# ASIC_3.net
KiCad netlist of a schematic drawn in Altium Designer
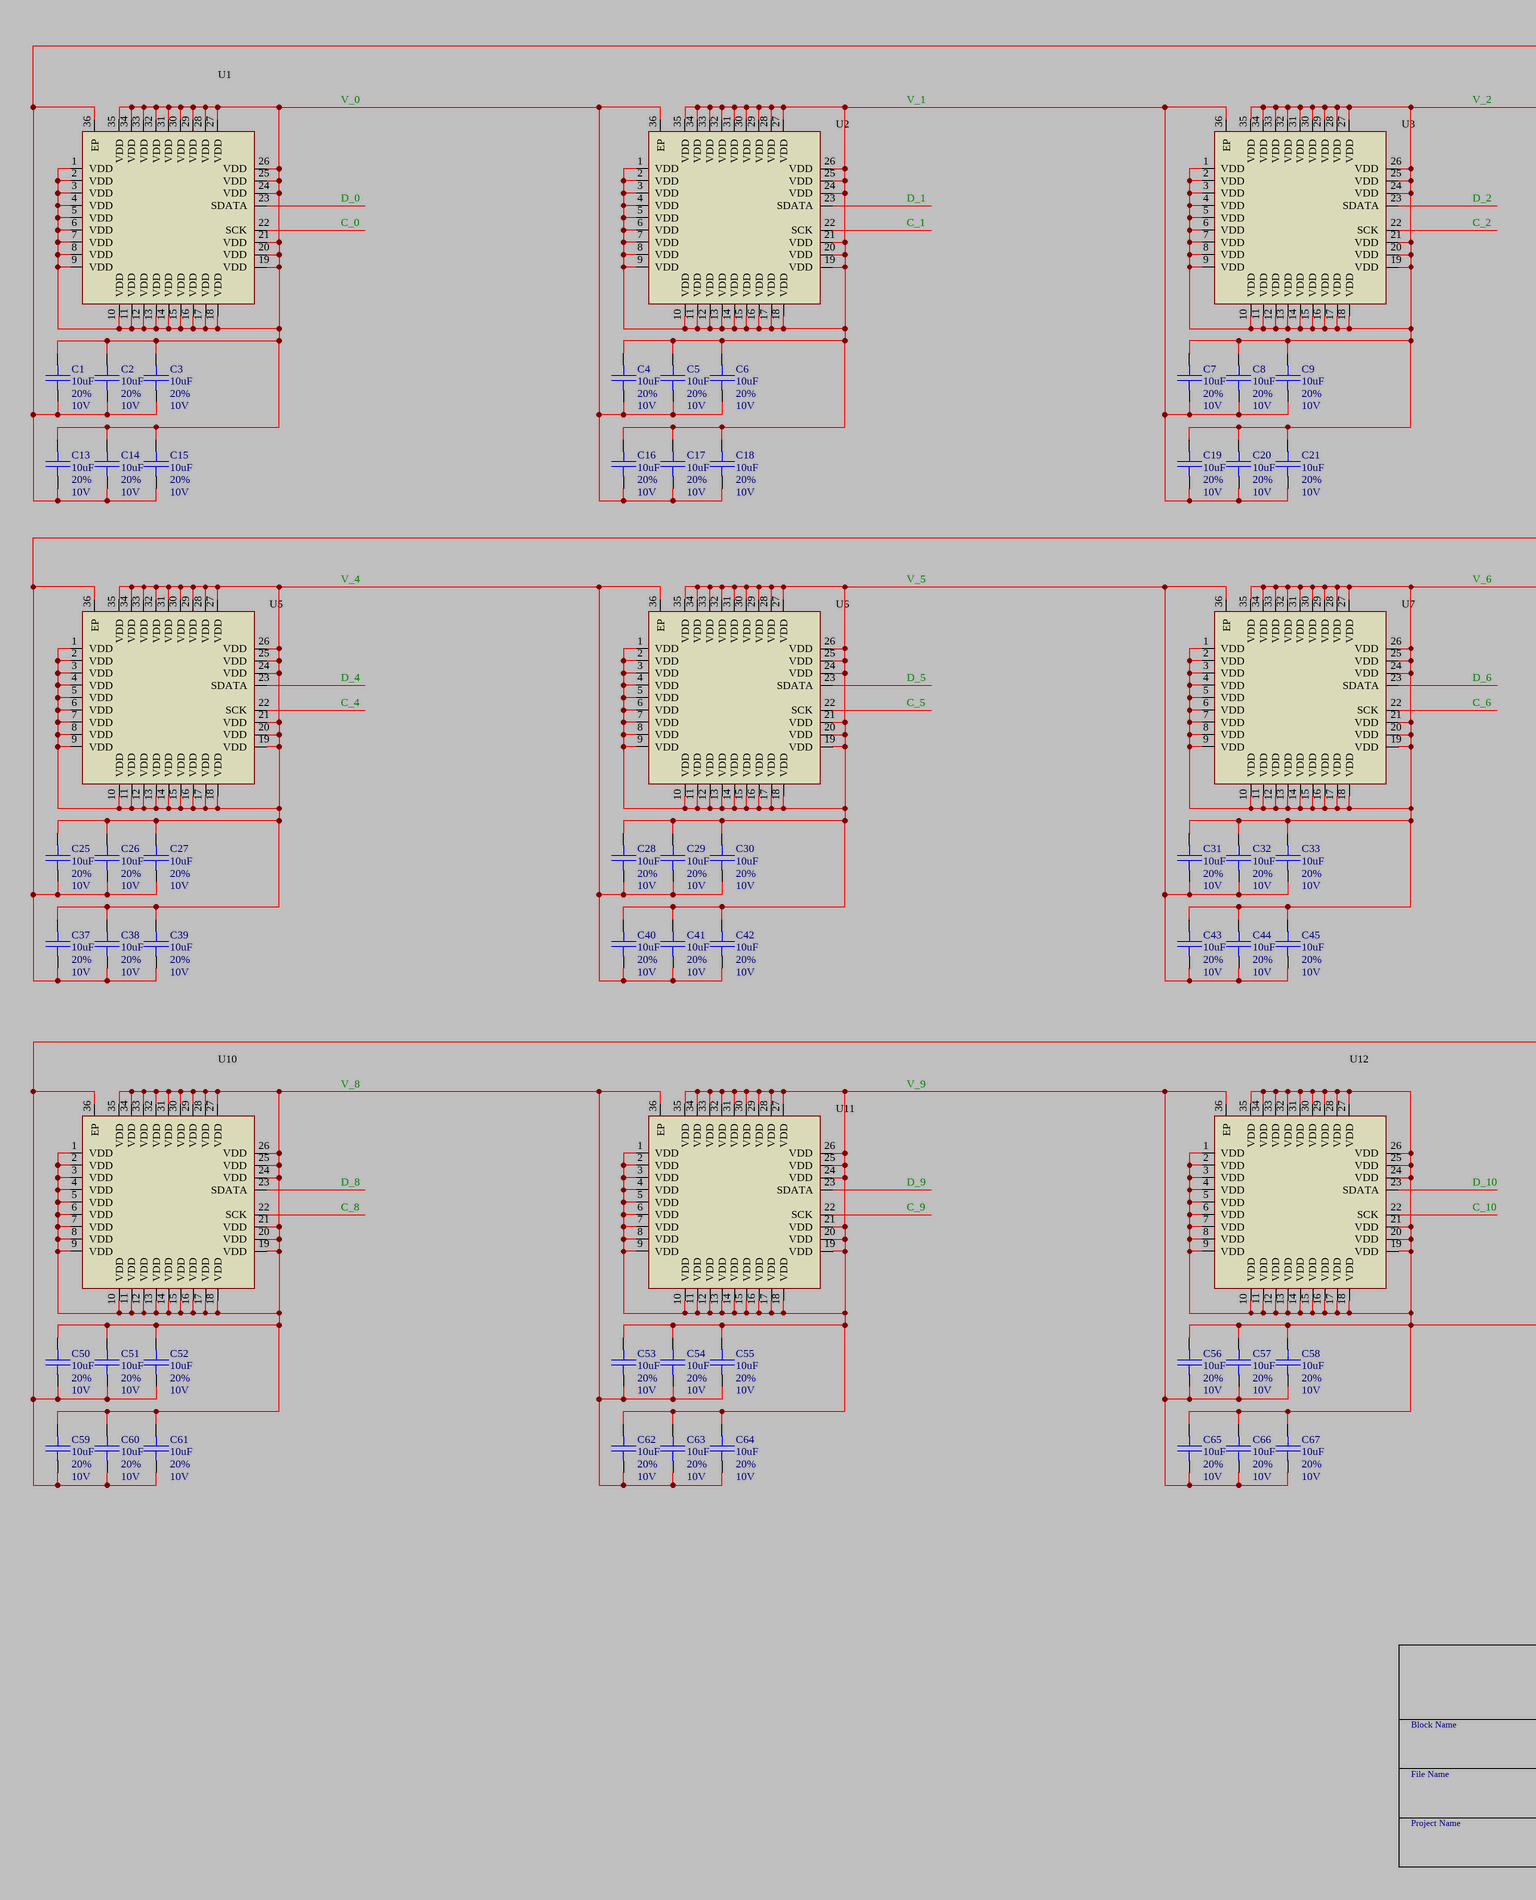
[diagram p0: ASIC_3.SchDoc, left]
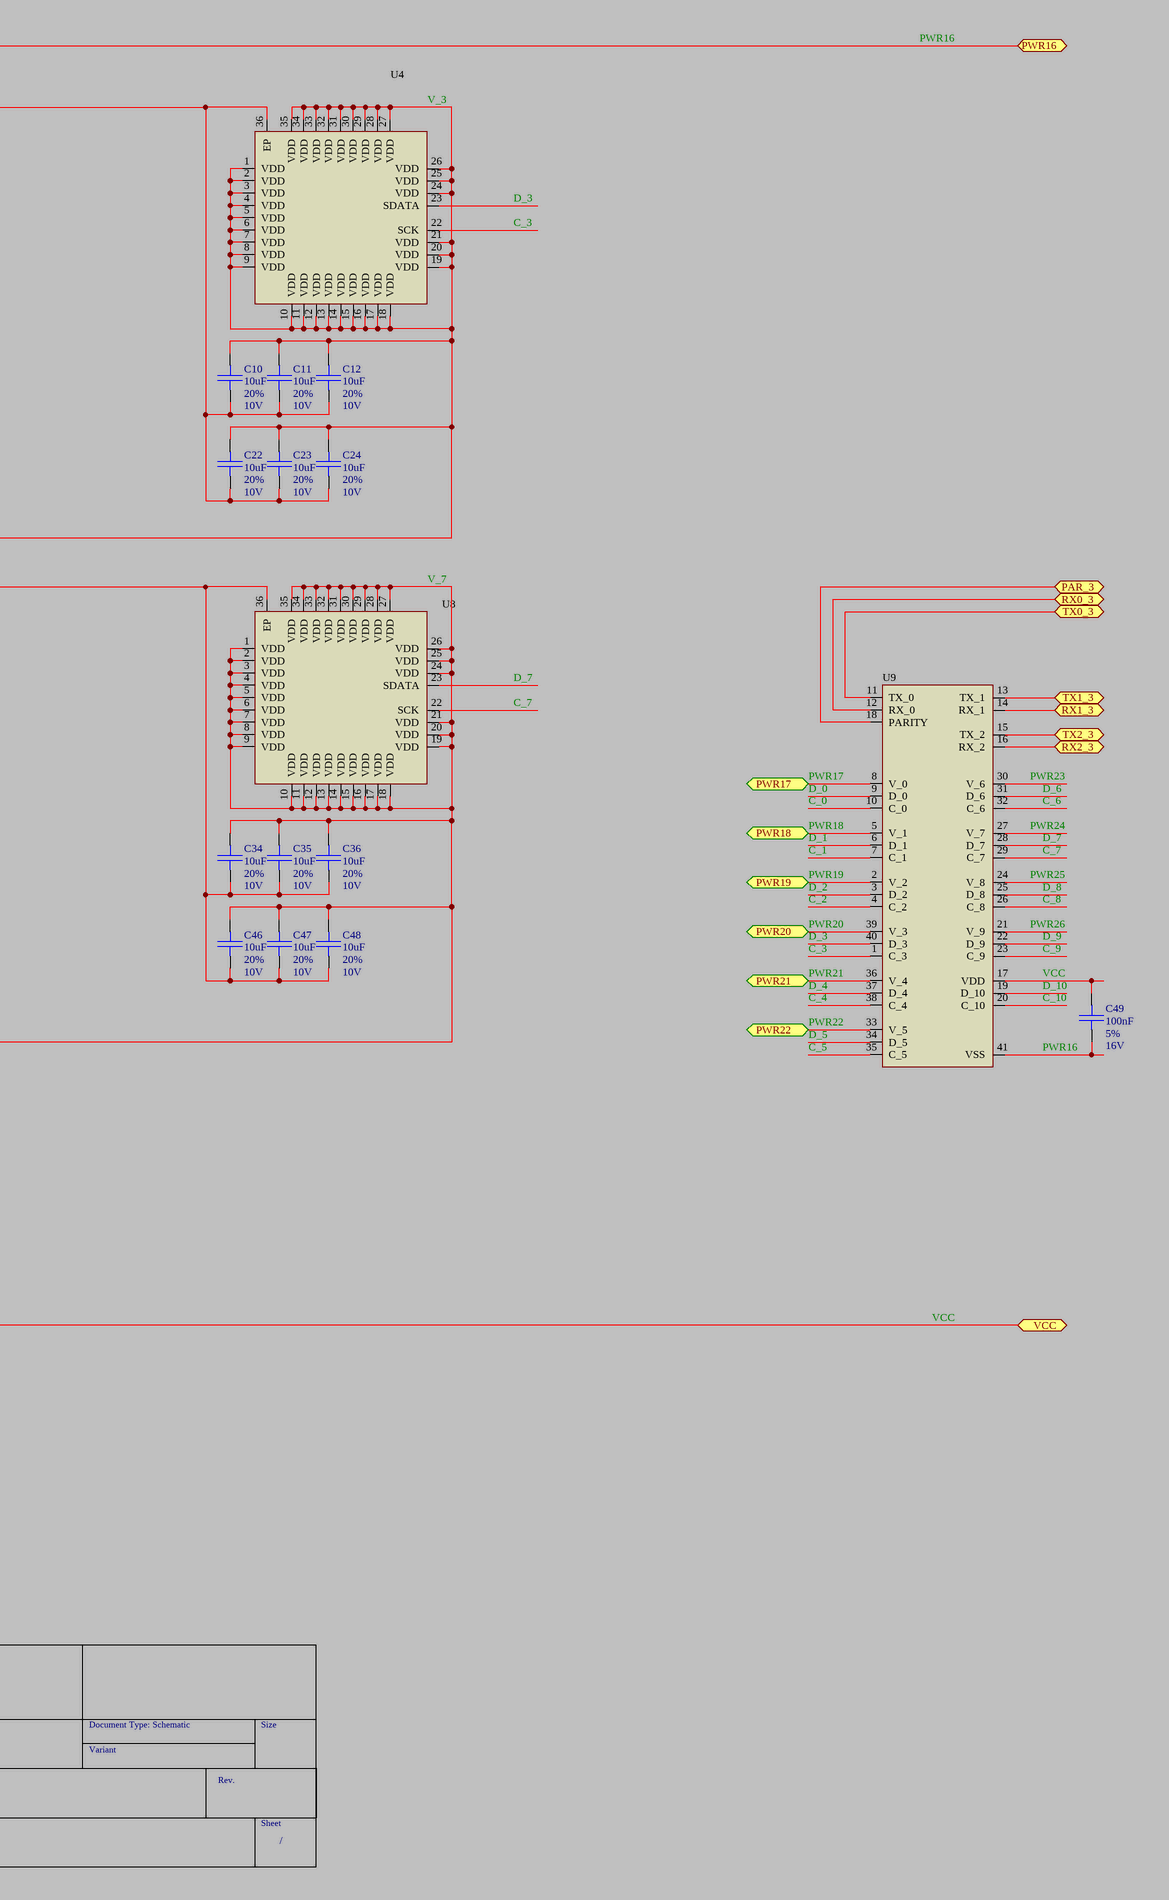
[diagram p1: ASIC_3.SchDoc, right]

(export (version "E")
  (design (tool "Eeschema 10.0.6"))
  (components
    (comp (ref "C1")
      (value "C")
      (footprint "SMD_0402_CAPC1005X70N")
      (fields
        (field (name "DB_PART_NUMBER") "CAP000047481")
        (field (name "DB_VALUE") "10uF")
        (field (name "DB_TOLERANCE") "20%")
        (field (name "DB_VOLTAGE") "10V")
        (field (name "DB_MANUFACTURER_PART") "SAMSUNG    CL05A106MP5NUNC")
        (field (name "DB_APPROVED_BY") "VSN")
      )
      (libsource (lib "Database_Libs1") (part "C"))
    )
    (comp (ref "C2")
      (value "C")
      (footprint "SMD_0402_CAPC1005X70N")
      (fields
        (field (name "DB_PART_NUMBER") "CAP000047481")
        (field (name "DB_VALUE") "10uF")
        (field (name "DB_TOLERANCE") "20%")
        (field (name "DB_VOLTAGE") "10V")
        (field (name "DB_MANUFACTURER_PART") "SAMSUNG    CL05A106MP5NUNC")
        (field (name "DB_APPROVED_BY") "VSN")
      )
      (libsource (lib "Database_Libs1") (part "C"))
    )
    (comp (ref "C3")
      (value "C")
      (footprint "SMD_0402_CAPC1005X70N")
      (fields
        (field (name "DB_PART_NUMBER") "CAP000047481")
        (field (name "DB_VALUE") "10uF")
        (field (name "DB_TOLERANCE") "20%")
        (field (name "DB_VOLTAGE") "10V")
        (field (name "DB_MANUFACTURER_PART") "SAMSUNG    CL05A106MP5NUNC")
        (field (name "DB_APPROVED_BY") "VSN")
      )
      (libsource (lib "Database_Libs1") (part "C"))
    )
    (comp (ref "C4")
      (value "C")
      (footprint "SMD_0402_CAPC1005X70N")
      (fields
        (field (name "DB_PART_NUMBER") "CAP000047481")
        (field (name "DB_VALUE") "10uF")
        (field (name "DB_TOLERANCE") "20%")
        (field (name "DB_VOLTAGE") "10V")
        (field (name "DB_MANUFACTURER_PART") "SAMSUNG    CL05A106MP5NUNC")
        (field (name "DB_APPROVED_BY") "VSN")
      )
      (libsource (lib "Database_Libs1") (part "C"))
    )
    (comp (ref "C5")
      (value "C")
      (footprint "SMD_0402_CAPC1005X70N")
      (fields
        (field (name "DB_PART_NUMBER") "CAP000047481")
        (field (name "DB_VALUE") "10uF")
        (field (name "DB_TOLERANCE") "20%")
        (field (name "DB_VOLTAGE") "10V")
        (field (name "DB_MANUFACTURER_PART") "SAMSUNG    CL05A106MP5NUNC")
        (field (name "DB_APPROVED_BY") "VSN")
      )
      (libsource (lib "Database_Libs1") (part "C"))
    )
    (comp (ref "C6")
      (value "C")
      (footprint "SMD_0402_CAPC1005X70N")
      (fields
        (field (name "DB_PART_NUMBER") "CAP000047481")
        (field (name "DB_VALUE") "10uF")
        (field (name "DB_TOLERANCE") "20%")
        (field (name "DB_VOLTAGE") "10V")
        (field (name "DB_MANUFACTURER_PART") "SAMSUNG    CL05A106MP5NUNC")
        (field (name "DB_APPROVED_BY") "VSN")
      )
      (libsource (lib "Database_Libs1") (part "C"))
    )
    (comp (ref "C7")
      (value "C")
      (footprint "SMD_0402_CAPC1005X70N")
      (fields
        (field (name "DB_PART_NUMBER") "CAP000047481")
        (field (name "DB_VALUE") "10uF")
        (field (name "DB_TOLERANCE") "20%")
        (field (name "DB_VOLTAGE") "10V")
        (field (name "DB_MANUFACTURER_PART") "SAMSUNG    CL05A106MP5NUNC")
        (field (name "DB_APPROVED_BY") "VSN")
      )
      (libsource (lib "Database_Libs1") (part "C"))
    )
    (comp (ref "C8")
      (value "C")
      (footprint "SMD_0402_CAPC1005X70N")
      (fields
        (field (name "DB_PART_NUMBER") "CAP000047481")
        (field (name "DB_VALUE") "10uF")
        (field (name "DB_TOLERANCE") "20%")
        (field (name "DB_VOLTAGE") "10V")
        (field (name "DB_MANUFACTURER_PART") "SAMSUNG    CL05A106MP5NUNC")
        (field (name "DB_APPROVED_BY") "VSN")
      )
      (libsource (lib "Database_Libs1") (part "C"))
    )
    (comp (ref "C9")
      (value "C")
      (footprint "SMD_0402_CAPC1005X70N")
      (fields
        (field (name "DB_PART_NUMBER") "CAP000047481")
        (field (name "DB_VALUE") "10uF")
        (field (name "DB_TOLERANCE") "20%")
        (field (name "DB_VOLTAGE") "10V")
        (field (name "DB_MANUFACTURER_PART") "SAMSUNG    CL05A106MP5NUNC")
        (field (name "DB_APPROVED_BY") "VSN")
      )
      (libsource (lib "Database_Libs1") (part "C"))
    )
    (comp (ref "C10")
      (value "C")
      (footprint "SMD_0402_CAPC1005X70N")
      (fields
        (field (name "DB_PART_NUMBER") "CAP000047481")
        (field (name "DB_VALUE") "10uF")
        (field (name "DB_TOLERANCE") "20%")
        (field (name "DB_VOLTAGE") "10V")
        (field (name "DB_MANUFACTURER_PART") "SAMSUNG    CL05A106MP5NUNC")
        (field (name "DB_APPROVED_BY") "VSN")
      )
      (libsource (lib "Database_Libs1") (part "C"))
    )
    (comp (ref "C11")
      (value "C")
      (footprint "SMD_0402_CAPC1005X70N")
      (fields
        (field (name "DB_PART_NUMBER") "CAP000047481")
        (field (name "DB_VALUE") "10uF")
        (field (name "DB_TOLERANCE") "20%")
        (field (name "DB_VOLTAGE") "10V")
        (field (name "DB_MANUFACTURER_PART") "SAMSUNG    CL05A106MP5NUNC")
        (field (name "DB_APPROVED_BY") "VSN")
      )
      (libsource (lib "Database_Libs1") (part "C"))
    )
    (comp (ref "C12")
      (value "C")
      (footprint "SMD_0402_CAPC1005X70N")
      (fields
        (field (name "DB_PART_NUMBER") "CAP000047481")
        (field (name "DB_VALUE") "10uF")
        (field (name "DB_TOLERANCE") "20%")
        (field (name "DB_VOLTAGE") "10V")
        (field (name "DB_MANUFACTURER_PART") "SAMSUNG    CL05A106MP5NUNC")
        (field (name "DB_APPROVED_BY") "VSN")
      )
      (libsource (lib "Database_Libs1") (part "C"))
    )
    (comp (ref "C13")
      (value "C")
      (footprint "SMD_0402_CAPC1005X70N")
      (fields
        (field (name "DB_PART_NUMBER") "CAP000047481")
        (field (name "DB_VALUE") "10uF")
        (field (name "DB_TOLERANCE") "20%")
        (field (name "DB_VOLTAGE") "10V")
        (field (name "DB_MANUFACTURER_PART") "SAMSUNG    CL05A106MP5NUNC")
        (field (name "DB_APPROVED_BY") "VSN")
      )
      (libsource (lib "Database_Libs1") (part "C"))
    )
    (comp (ref "C14")
      (value "C")
      (footprint "SMD_0402_CAPC1005X70N")
      (fields
        (field (name "DB_PART_NUMBER") "CAP000047481")
        (field (name "DB_VALUE") "10uF")
        (field (name "DB_TOLERANCE") "20%")
        (field (name "DB_VOLTAGE") "10V")
        (field (name "DB_MANUFACTURER_PART") "SAMSUNG    CL05A106MP5NUNC")
        (field (name "DB_APPROVED_BY") "VSN")
      )
      (libsource (lib "Database_Libs1") (part "C"))
    )
    (comp (ref "C15")
      (value "C")
      (footprint "SMD_0402_CAPC1005X70N")
      (fields
        (field (name "DB_PART_NUMBER") "CAP000047481")
        (field (name "DB_VALUE") "10uF")
        (field (name "DB_TOLERANCE") "20%")
        (field (name "DB_VOLTAGE") "10V")
        (field (name "DB_MANUFACTURER_PART") "SAMSUNG    CL05A106MP5NUNC")
        (field (name "DB_APPROVED_BY") "VSN")
      )
      (libsource (lib "Database_Libs1") (part "C"))
    )
    (comp (ref "C16")
      (value "C")
      (footprint "SMD_0402_CAPC1005X70N")
      (fields
        (field (name "DB_PART_NUMBER") "CAP000047481")
        (field (name "DB_VALUE") "10uF")
        (field (name "DB_TOLERANCE") "20%")
        (field (name "DB_VOLTAGE") "10V")
        (field (name "DB_MANUFACTURER_PART") "SAMSUNG    CL05A106MP5NUNC")
        (field (name "DB_APPROVED_BY") "VSN")
      )
      (libsource (lib "Database_Libs1") (part "C"))
    )
    (comp (ref "C17")
      (value "C")
      (footprint "SMD_0402_CAPC1005X70N")
      (fields
        (field (name "DB_PART_NUMBER") "CAP000047481")
        (field (name "DB_VALUE") "10uF")
        (field (name "DB_TOLERANCE") "20%")
        (field (name "DB_VOLTAGE") "10V")
        (field (name "DB_MANUFACTURER_PART") "SAMSUNG    CL05A106MP5NUNC")
        (field (name "DB_APPROVED_BY") "VSN")
      )
      (libsource (lib "Database_Libs1") (part "C"))
    )
    (comp (ref "C18")
      (value "C")
      (footprint "SMD_0402_CAPC1005X70N")
      (fields
        (field (name "DB_PART_NUMBER") "CAP000047481")
        (field (name "DB_VALUE") "10uF")
        (field (name "DB_TOLERANCE") "20%")
        (field (name "DB_VOLTAGE") "10V")
        (field (name "DB_MANUFACTURER_PART") "SAMSUNG    CL05A106MP5NUNC")
        (field (name "DB_APPROVED_BY") "VSN")
      )
      (libsource (lib "Database_Libs1") (part "C"))
    )
    (comp (ref "C19")
      (value "C")
      (footprint "SMD_0402_CAPC1005X70N")
      (fields
        (field (name "DB_PART_NUMBER") "CAP000047481")
        (field (name "DB_VALUE") "10uF")
        (field (name "DB_TOLERANCE") "20%")
        (field (name "DB_VOLTAGE") "10V")
        (field (name "DB_MANUFACTURER_PART") "SAMSUNG    CL05A106MP5NUNC")
        (field (name "DB_APPROVED_BY") "VSN")
      )
      (libsource (lib "Database_Libs1") (part "C"))
    )
    (comp (ref "C20")
      (value "C")
      (footprint "SMD_0402_CAPC1005X70N")
      (fields
        (field (name "DB_PART_NUMBER") "CAP000047481")
        (field (name "DB_VALUE") "10uF")
        (field (name "DB_TOLERANCE") "20%")
        (field (name "DB_VOLTAGE") "10V")
        (field (name "DB_MANUFACTURER_PART") "SAMSUNG    CL05A106MP5NUNC")
        (field (name "DB_APPROVED_BY") "VSN")
      )
      (libsource (lib "Database_Libs1") (part "C"))
    )
    (comp (ref "C21")
      (value "C")
      (footprint "SMD_0402_CAPC1005X70N")
      (fields
        (field (name "DB_PART_NUMBER") "CAP000047481")
        (field (name "DB_VALUE") "10uF")
        (field (name "DB_TOLERANCE") "20%")
        (field (name "DB_VOLTAGE") "10V")
        (field (name "DB_MANUFACTURER_PART") "SAMSUNG    CL05A106MP5NUNC")
        (field (name "DB_APPROVED_BY") "VSN")
      )
      (libsource (lib "Database_Libs1") (part "C"))
    )
    (comp (ref "C22")
      (value "C")
      (footprint "SMD_0402_CAPC1005X70N")
      (fields
        (field (name "DB_PART_NUMBER") "CAP000047481")
        (field (name "DB_VALUE") "10uF")
        (field (name "DB_TOLERANCE") "20%")
        (field (name "DB_VOLTAGE") "10V")
        (field (name "DB_MANUFACTURER_PART") "SAMSUNG    CL05A106MP5NUNC")
        (field (name "DB_APPROVED_BY") "VSN")
      )
      (libsource (lib "Database_Libs1") (part "C"))
    )
    (comp (ref "C23")
      (value "C")
      (footprint "SMD_0402_CAPC1005X70N")
      (fields
        (field (name "DB_PART_NUMBER") "CAP000047481")
        (field (name "DB_VALUE") "10uF")
        (field (name "DB_TOLERANCE") "20%")
        (field (name "DB_VOLTAGE") "10V")
        (field (name "DB_MANUFACTURER_PART") "SAMSUNG    CL05A106MP5NUNC")
        (field (name "DB_APPROVED_BY") "VSN")
      )
      (libsource (lib "Database_Libs1") (part "C"))
    )
    (comp (ref "C24")
      (value "C")
      (footprint "SMD_0402_CAPC1005X70N")
      (fields
        (field (name "DB_PART_NUMBER") "CAP000047481")
        (field (name "DB_VALUE") "10uF")
        (field (name "DB_TOLERANCE") "20%")
        (field (name "DB_VOLTAGE") "10V")
        (field (name "DB_MANUFACTURER_PART") "SAMSUNG    CL05A106MP5NUNC")
        (field (name "DB_APPROVED_BY") "VSN")
      )
      (libsource (lib "Database_Libs1") (part "C"))
    )
    (comp (ref "C25")
      (value "C")
      (footprint "SMD_0402_CAPC1005X70N")
      (fields
        (field (name "DB_PART_NUMBER") "CAP000047481")
        (field (name "DB_VALUE") "10uF")
        (field (name "DB_TOLERANCE") "20%")
        (field (name "DB_VOLTAGE") "10V")
        (field (name "DB_MANUFACTURER_PART") "SAMSUNG    CL05A106MP5NUNC")
        (field (name "DB_APPROVED_BY") "VSN")
      )
      (libsource (lib "Database_Libs1") (part "C"))
    )
    (comp (ref "C26")
      (value "C")
      (footprint "SMD_0402_CAPC1005X70N")
      (fields
        (field (name "DB_PART_NUMBER") "CAP000047481")
        (field (name "DB_VALUE") "10uF")
        (field (name "DB_TOLERANCE") "20%")
        (field (name "DB_VOLTAGE") "10V")
        (field (name "DB_MANUFACTURER_PART") "SAMSUNG    CL05A106MP5NUNC")
        (field (name "DB_APPROVED_BY") "VSN")
      )
      (libsource (lib "Database_Libs1") (part "C"))
    )
    (comp (ref "C27")
      (value "C")
      (footprint "SMD_0402_CAPC1005X70N")
      (fields
        (field (name "DB_PART_NUMBER") "CAP000047481")
        (field (name "DB_VALUE") "10uF")
        (field (name "DB_TOLERANCE") "20%")
        (field (name "DB_VOLTAGE") "10V")
        (field (name "DB_MANUFACTURER_PART") "SAMSUNG    CL05A106MP5NUNC")
        (field (name "DB_APPROVED_BY") "VSN")
      )
      (libsource (lib "Database_Libs1") (part "C"))
    )
    (comp (ref "C28")
      (value "C")
      (footprint "SMD_0402_CAPC1005X70N")
      (fields
        (field (name "DB_PART_NUMBER") "CAP000047481")
        (field (name "DB_VALUE") "10uF")
        (field (name "DB_TOLERANCE") "20%")
        (field (name "DB_VOLTAGE") "10V")
        (field (name "DB_MANUFACTURER_PART") "SAMSUNG    CL05A106MP5NUNC")
        (field (name "DB_APPROVED_BY") "VSN")
      )
      (libsource (lib "Database_Libs1") (part "C"))
    )
    (comp (ref "C29")
      (value "C")
      (footprint "SMD_0402_CAPC1005X70N")
      (fields
        (field (name "DB_PART_NUMBER") "CAP000047481")
        (field (name "DB_VALUE") "10uF")
        (field (name "DB_TOLERANCE") "20%")
        (field (name "DB_VOLTAGE") "10V")
        (field (name "DB_MANUFACTURER_PART") "SAMSUNG    CL05A106MP5NUNC")
        (field (name "DB_APPROVED_BY") "VSN")
      )
      (libsource (lib "Database_Libs1") (part "C"))
    )
    (comp (ref "C30")
      (value "C")
      (footprint "SMD_0402_CAPC1005X70N")
      (fields
        (field (name "DB_PART_NUMBER") "CAP000047481")
        (field (name "DB_VALUE") "10uF")
        (field (name "DB_TOLERANCE") "20%")
        (field (name "DB_VOLTAGE") "10V")
        (field (name "DB_MANUFACTURER_PART") "SAMSUNG    CL05A106MP5NUNC")
        (field (name "DB_APPROVED_BY") "VSN")
      )
      (libsource (lib "Database_Libs1") (part "C"))
    )
    (comp (ref "C31")
      (value "C")
      (footprint "SMD_0402_CAPC1005X70N")
      (fields
        (field (name "DB_PART_NUMBER") "CAP000047481")
        (field (name "DB_VALUE") "10uF")
        (field (name "DB_TOLERANCE") "20%")
        (field (name "DB_VOLTAGE") "10V")
        (field (name "DB_MANUFACTURER_PART") "SAMSUNG    CL05A106MP5NUNC")
        (field (name "DB_APPROVED_BY") "VSN")
      )
      (libsource (lib "Database_Libs1") (part "C"))
    )
    (comp (ref "C32")
      (value "C")
      (footprint "SMD_0402_CAPC1005X70N")
      (fields
        (field (name "DB_PART_NUMBER") "CAP000047481")
        (field (name "DB_VALUE") "10uF")
        (field (name "DB_TOLERANCE") "20%")
        (field (name "DB_VOLTAGE") "10V")
        (field (name "DB_MANUFACTURER_PART") "SAMSUNG    CL05A106MP5NUNC")
        (field (name "DB_APPROVED_BY") "VSN")
      )
      (libsource (lib "Database_Libs1") (part "C"))
    )
    (comp (ref "C33")
      (value "C")
      (footprint "SMD_0402_CAPC1005X70N")
      (fields
        (field (name "DB_PART_NUMBER") "CAP000047481")
        (field (name "DB_VALUE") "10uF")
        (field (name "DB_TOLERANCE") "20%")
        (field (name "DB_VOLTAGE") "10V")
        (field (name "DB_MANUFACTURER_PART") "SAMSUNG    CL05A106MP5NUNC")
        (field (name "DB_APPROVED_BY") "VSN")
      )
      (libsource (lib "Database_Libs1") (part "C"))
    )
    (comp (ref "C34")
      (value "C")
      (footprint "SMD_0402_CAPC1005X70N")
      (fields
        (field (name "DB_PART_NUMBER") "CAP000047481")
        (field (name "DB_VALUE") "10uF")
        (field (name "DB_TOLERANCE") "20%")
        (field (name "DB_VOLTAGE") "10V")
        (field (name "DB_MANUFACTURER_PART") "SAMSUNG    CL05A106MP5NUNC")
        (field (name "DB_APPROVED_BY") "VSN")
      )
      (libsource (lib "Database_Libs1") (part "C"))
    )
    (comp (ref "C35")
      (value "C")
      (footprint "SMD_0402_CAPC1005X70N")
      (fields
        (field (name "DB_PART_NUMBER") "CAP000047481")
        (field (name "DB_VALUE") "10uF")
        (field (name "DB_TOLERANCE") "20%")
        (field (name "DB_VOLTAGE") "10V")
        (field (name "DB_MANUFACTURER_PART") "SAMSUNG    CL05A106MP5NUNC")
        (field (name "DB_APPROVED_BY") "VSN")
      )
      (libsource (lib "Database_Libs1") (part "C"))
    )
    (comp (ref "C36")
      (value "C")
      (footprint "SMD_0402_CAPC1005X70N")
      (fields
        (field (name "DB_PART_NUMBER") "CAP000047481")
        (field (name "DB_VALUE") "10uF")
        (field (name "DB_TOLERANCE") "20%")
        (field (name "DB_VOLTAGE") "10V")
        (field (name "DB_MANUFACTURER_PART") "SAMSUNG    CL05A106MP5NUNC")
        (field (name "DB_APPROVED_BY") "VSN")
      )
      (libsource (lib "Database_Libs1") (part "C"))
    )
    (comp (ref "C37")
      (value "C")
      (footprint "SMD_0402_CAPC1005X70N")
      (fields
        (field (name "DB_PART_NUMBER") "CAP000047481")
        (field (name "DB_VALUE") "10uF")
        (field (name "DB_TOLERANCE") "20%")
        (field (name "DB_VOLTAGE") "10V")
        (field (name "DB_MANUFACTURER_PART") "SAMSUNG    CL05A106MP5NUNC")
        (field (name "DB_APPROVED_BY") "VSN")
      )
      (libsource (lib "Database_Libs1") (part "C"))
    )
    (comp (ref "C38")
      (value "C")
      (footprint "SMD_0402_CAPC1005X70N")
      (fields
        (field (name "DB_PART_NUMBER") "CAP000047481")
        (field (name "DB_VALUE") "10uF")
        (field (name "DB_TOLERANCE") "20%")
        (field (name "DB_VOLTAGE") "10V")
        (field (name "DB_MANUFACTURER_PART") "SAMSUNG    CL05A106MP5NUNC")
        (field (name "DB_APPROVED_BY") "VSN")
      )
      (libsource (lib "Database_Libs1") (part "C"))
    )
    (comp (ref "C39")
      (value "C")
      (footprint "SMD_0402_CAPC1005X70N")
      (fields
        (field (name "DB_PART_NUMBER") "CAP000047481")
        (field (name "DB_VALUE") "10uF")
        (field (name "DB_TOLERANCE") "20%")
        (field (name "DB_VOLTAGE") "10V")
        (field (name "DB_MANUFACTURER_PART") "SAMSUNG    CL05A106MP5NUNC")
        (field (name "DB_APPROVED_BY") "VSN")
      )
      (libsource (lib "Database_Libs1") (part "C"))
    )
    (comp (ref "C40")
      (value "C")
      (footprint "SMD_0402_CAPC1005X70N")
      (fields
        (field (name "DB_PART_NUMBER") "CAP000047481")
        (field (name "DB_VALUE") "10uF")
        (field (name "DB_TOLERANCE") "20%")
        (field (name "DB_VOLTAGE") "10V")
        (field (name "DB_MANUFACTURER_PART") "SAMSUNG    CL05A106MP5NUNC")
        (field (name "DB_APPROVED_BY") "VSN")
      )
      (libsource (lib "Database_Libs1") (part "C"))
    )
    (comp (ref "C41")
      (value "C")
      (footprint "SMD_0402_CAPC1005X70N")
      (fields
        (field (name "DB_PART_NUMBER") "CAP000047481")
        (field (name "DB_VALUE") "10uF")
        (field (name "DB_TOLERANCE") "20%")
        (field (name "DB_VOLTAGE") "10V")
        (field (name "DB_MANUFACTURER_PART") "SAMSUNG    CL05A106MP5NUNC")
        (field (name "DB_APPROVED_BY") "VSN")
      )
      (libsource (lib "Database_Libs1") (part "C"))
    )
    (comp (ref "C42")
      (value "C")
      (footprint "SMD_0402_CAPC1005X70N")
      (fields
        (field (name "DB_PART_NUMBER") "CAP000047481")
        (field (name "DB_VALUE") "10uF")
        (field (name "DB_TOLERANCE") "20%")
        (field (name "DB_VOLTAGE") "10V")
        (field (name "DB_MANUFACTURER_PART") "SAMSUNG    CL05A106MP5NUNC")
        (field (name "DB_APPROVED_BY") "VSN")
      )
      (libsource (lib "Database_Libs1") (part "C"))
    )
    (comp (ref "C43")
      (value "C")
      (footprint "SMD_0402_CAPC1005X70N")
      (fields
        (field (name "DB_PART_NUMBER") "CAP000047481")
        (field (name "DB_VALUE") "10uF")
        (field (name "DB_TOLERANCE") "20%")
        (field (name "DB_VOLTAGE") "10V")
        (field (name "DB_MANUFACTURER_PART") "SAMSUNG    CL05A106MP5NUNC")
        (field (name "DB_APPROVED_BY") "VSN")
      )
      (libsource (lib "Database_Libs1") (part "C"))
    )
    (comp (ref "C44")
      (value "C")
      (footprint "SMD_0402_CAPC1005X70N")
      (fields
        (field (name "DB_PART_NUMBER") "CAP000047481")
        (field (name "DB_VALUE") "10uF")
        (field (name "DB_TOLERANCE") "20%")
        (field (name "DB_VOLTAGE") "10V")
        (field (name "DB_MANUFACTURER_PART") "SAMSUNG    CL05A106MP5NUNC")
        (field (name "DB_APPROVED_BY") "VSN")
      )
      (libsource (lib "Database_Libs1") (part "C"))
    )
    (comp (ref "C45")
      (value "C")
      (footprint "SMD_0402_CAPC1005X70N")
      (fields
        (field (name "DB_PART_NUMBER") "CAP000047481")
        (field (name "DB_VALUE") "10uF")
        (field (name "DB_TOLERANCE") "20%")
        (field (name "DB_VOLTAGE") "10V")
        (field (name "DB_MANUFACTURER_PART") "SAMSUNG    CL05A106MP5NUNC")
        (field (name "DB_APPROVED_BY") "VSN")
      )
      (libsource (lib "Database_Libs1") (part "C"))
    )
    (comp (ref "C46")
      (value "C")
      (footprint "SMD_0402_CAPC1005X70N")
      (fields
        (field (name "DB_PART_NUMBER") "CAP000047481")
        (field (name "DB_VALUE") "10uF")
        (field (name "DB_TOLERANCE") "20%")
        (field (name "DB_VOLTAGE") "10V")
        (field (name "DB_MANUFACTURER_PART") "SAMSUNG    CL05A106MP5NUNC")
        (field (name "DB_APPROVED_BY") "VSN")
      )
      (libsource (lib "Database_Libs1") (part "C"))
    )
    (comp (ref "C47")
      (value "C")
      (footprint "SMD_0402_CAPC1005X70N")
      (fields
        (field (name "DB_PART_NUMBER") "CAP000047481")
        (field (name "DB_VALUE") "10uF")
        (field (name "DB_TOLERANCE") "20%")
        (field (name "DB_VOLTAGE") "10V")
        (field (name "DB_MANUFACTURER_PART") "SAMSUNG    CL05A106MP5NUNC")
        (field (name "DB_APPROVED_BY") "VSN")
      )
      (libsource (lib "Database_Libs1") (part "C"))
    )
    (comp (ref "C48")
      (value "C")
      (footprint "SMD_0402_CAPC1005X70N")
      (fields
        (field (name "DB_PART_NUMBER") "CAP000047481")
        (field (name "DB_VALUE") "10uF")
        (field (name "DB_TOLERANCE") "20%")
        (field (name "DB_VOLTAGE") "10V")
        (field (name "DB_MANUFACTURER_PART") "SAMSUNG    CL05A106MP5NUNC")
        (field (name "DB_APPROVED_BY") "VSN")
      )
      (libsource (lib "Database_Libs1") (part "C"))
    )
    (comp (ref "C49")
      (value "C")
      (footprint "SMD_0603_CAPC1608X95N")
      (fields
        (field (name "DB_PART_NUMBER") "CAP000027134")
        (field (name "DB_VALUE") "100nF")
        (field (name "DB_TOLERANCE") "5%")
        (field (name "DB_VOLTAGE") "16V")
        (field (name "DB_MANUFACTURER_PART") "KEMET    C0603C104J4RAC")
      )
      (libsource (lib "Database_Libs1") (part "C"))
    )
    (comp (ref "C50")
      (value "C")
      (footprint "SMD_0402_CAPC1005X70N")
      (fields
        (field (name "DB_PART_NUMBER") "CAP000047481")
        (field (name "DB_VALUE") "10uF")
        (field (name "DB_TOLERANCE") "20%")
        (field (name "DB_VOLTAGE") "10V")
        (field (name "DB_MANUFACTURER_PART") "SAMSUNG    CL05A106MP5NUNC")
        (field (name "DB_APPROVED_BY") "VSN")
      )
      (libsource (lib "Database_Libs1") (part "C"))
    )
    (comp (ref "C51")
      (value "C")
      (footprint "SMD_0402_CAPC1005X70N")
      (fields
        (field (name "DB_PART_NUMBER") "CAP000047481")
        (field (name "DB_VALUE") "10uF")
        (field (name "DB_TOLERANCE") "20%")
        (field (name "DB_VOLTAGE") "10V")
        (field (name "DB_MANUFACTURER_PART") "SAMSUNG    CL05A106MP5NUNC")
        (field (name "DB_APPROVED_BY") "VSN")
      )
      (libsource (lib "Database_Libs1") (part "C"))
    )
    (comp (ref "C52")
      (value "C")
      (footprint "SMD_0402_CAPC1005X70N")
      (fields
        (field (name "DB_PART_NUMBER") "CAP000047481")
        (field (name "DB_VALUE") "10uF")
        (field (name "DB_TOLERANCE") "20%")
        (field (name "DB_VOLTAGE") "10V")
        (field (name "DB_MANUFACTURER_PART") "SAMSUNG    CL05A106MP5NUNC")
        (field (name "DB_APPROVED_BY") "VSN")
      )
      (libsource (lib "Database_Libs1") (part "C"))
    )
    (comp (ref "C53")
      (value "C")
      (footprint "SMD_0402_CAPC1005X70N")
      (fields
        (field (name "DB_PART_NUMBER") "CAP000047481")
        (field (name "DB_VALUE") "10uF")
        (field (name "DB_TOLERANCE") "20%")
        (field (name "DB_VOLTAGE") "10V")
        (field (name "DB_MANUFACTURER_PART") "SAMSUNG    CL05A106MP5NUNC")
        (field (name "DB_APPROVED_BY") "VSN")
      )
      (libsource (lib "Database_Libs1") (part "C"))
    )
    (comp (ref "C54")
      (value "C")
      (footprint "SMD_0402_CAPC1005X70N")
      (fields
        (field (name "DB_PART_NUMBER") "CAP000047481")
        (field (name "DB_VALUE") "10uF")
        (field (name "DB_TOLERANCE") "20%")
        (field (name "DB_VOLTAGE") "10V")
        (field (name "DB_MANUFACTURER_PART") "SAMSUNG    CL05A106MP5NUNC")
        (field (name "DB_APPROVED_BY") "VSN")
      )
      (libsource (lib "Database_Libs1") (part "C"))
    )
    (comp (ref "C55")
      (value "C")
      (footprint "SMD_0402_CAPC1005X70N")
      (fields
        (field (name "DB_PART_NUMBER") "CAP000047481")
        (field (name "DB_VALUE") "10uF")
        (field (name "DB_TOLERANCE") "20%")
        (field (name "DB_VOLTAGE") "10V")
        (field (name "DB_MANUFACTURER_PART") "SAMSUNG    CL05A106MP5NUNC")
        (field (name "DB_APPROVED_BY") "VSN")
      )
      (libsource (lib "Database_Libs1") (part "C"))
    )
    (comp (ref "C56")
      (value "C")
      (footprint "SMD_0402_CAPC1005X70N")
      (fields
        (field (name "DB_PART_NUMBER") "CAP000047481")
        (field (name "DB_VALUE") "10uF")
        (field (name "DB_TOLERANCE") "20%")
        (field (name "DB_VOLTAGE") "10V")
        (field (name "DB_MANUFACTURER_PART") "SAMSUNG    CL05A106MP5NUNC")
        (field (name "DB_APPROVED_BY") "VSN")
      )
      (libsource (lib "Database_Libs1") (part "C"))
    )
    (comp (ref "C57")
      (value "C")
      (footprint "SMD_0402_CAPC1005X70N")
      (fields
        (field (name "DB_PART_NUMBER") "CAP000047481")
        (field (name "DB_VALUE") "10uF")
        (field (name "DB_TOLERANCE") "20%")
        (field (name "DB_VOLTAGE") "10V")
        (field (name "DB_MANUFACTURER_PART") "SAMSUNG    CL05A106MP5NUNC")
        (field (name "DB_APPROVED_BY") "VSN")
      )
      (libsource (lib "Database_Libs1") (part "C"))
    )
    (comp (ref "C58")
      (value "C")
      (footprint "SMD_0402_CAPC1005X70N")
      (fields
        (field (name "DB_PART_NUMBER") "CAP000047481")
        (field (name "DB_VALUE") "10uF")
        (field (name "DB_TOLERANCE") "20%")
        (field (name "DB_VOLTAGE") "10V")
        (field (name "DB_MANUFACTURER_PART") "SAMSUNG    CL05A106MP5NUNC")
        (field (name "DB_APPROVED_BY") "VSN")
      )
      (libsource (lib "Database_Libs1") (part "C"))
    )
    (comp (ref "C59")
      (value "C")
      (footprint "SMD_0402_CAPC1005X70N")
      (fields
        (field (name "DB_PART_NUMBER") "CAP000047481")
        (field (name "DB_VALUE") "10uF")
        (field (name "DB_TOLERANCE") "20%")
        (field (name "DB_VOLTAGE") "10V")
        (field (name "DB_MANUFACTURER_PART") "SAMSUNG    CL05A106MP5NUNC")
        (field (name "DB_APPROVED_BY") "VSN")
      )
      (libsource (lib "Database_Libs1") (part "C"))
    )
    (comp (ref "C60")
      (value "C")
      (footprint "SMD_0402_CAPC1005X70N")
      (fields
        (field (name "DB_PART_NUMBER") "CAP000047481")
        (field (name "DB_VALUE") "10uF")
        (field (name "DB_TOLERANCE") "20%")
        (field (name "DB_VOLTAGE") "10V")
        (field (name "DB_MANUFACTURER_PART") "SAMSUNG    CL05A106MP5NUNC")
        (field (name "DB_APPROVED_BY") "VSN")
      )
      (libsource (lib "Database_Libs1") (part "C"))
    )
    (comp (ref "C61")
      (value "C")
      (footprint "SMD_0402_CAPC1005X70N")
      (fields
        (field (name "DB_PART_NUMBER") "CAP000047481")
        (field (name "DB_VALUE") "10uF")
        (field (name "DB_TOLERANCE") "20%")
        (field (name "DB_VOLTAGE") "10V")
        (field (name "DB_MANUFACTURER_PART") "SAMSUNG    CL05A106MP5NUNC")
        (field (name "DB_APPROVED_BY") "VSN")
      )
      (libsource (lib "Database_Libs1") (part "C"))
    )
    (comp (ref "C62")
      (value "C")
      (footprint "SMD_0402_CAPC1005X70N")
      (fields
        (field (name "DB_PART_NUMBER") "CAP000047481")
        (field (name "DB_VALUE") "10uF")
        (field (name "DB_TOLERANCE") "20%")
        (field (name "DB_VOLTAGE") "10V")
        (field (name "DB_MANUFACTURER_PART") "SAMSUNG    CL05A106MP5NUNC")
        (field (name "DB_APPROVED_BY") "VSN")
      )
      (libsource (lib "Database_Libs1") (part "C"))
    )
    (comp (ref "C63")
      (value "C")
      (footprint "SMD_0402_CAPC1005X70N")
      (fields
        (field (name "DB_PART_NUMBER") "CAP000047481")
        (field (name "DB_VALUE") "10uF")
        (field (name "DB_TOLERANCE") "20%")
        (field (name "DB_VOLTAGE") "10V")
        (field (name "DB_MANUFACTURER_PART") "SAMSUNG    CL05A106MP5NUNC")
        (field (name "DB_APPROVED_BY") "VSN")
      )
      (libsource (lib "Database_Libs1") (part "C"))
    )
    (comp (ref "C64")
      (value "C")
      (footprint "SMD_0402_CAPC1005X70N")
      (fields
        (field (name "DB_PART_NUMBER") "CAP000047481")
        (field (name "DB_VALUE") "10uF")
        (field (name "DB_TOLERANCE") "20%")
        (field (name "DB_VOLTAGE") "10V")
        (field (name "DB_MANUFACTURER_PART") "SAMSUNG    CL05A106MP5NUNC")
        (field (name "DB_APPROVED_BY") "VSN")
      )
      (libsource (lib "Database_Libs1") (part "C"))
    )
    (comp (ref "C65")
      (value "C")
      (footprint "SMD_0402_CAPC1005X70N")
      (fields
        (field (name "DB_PART_NUMBER") "CAP000047481")
        (field (name "DB_VALUE") "10uF")
        (field (name "DB_TOLERANCE") "20%")
        (field (name "DB_VOLTAGE") "10V")
        (field (name "DB_MANUFACTURER_PART") "SAMSUNG    CL05A106MP5NUNC")
        (field (name "DB_APPROVED_BY") "VSN")
      )
      (libsource (lib "Database_Libs1") (part "C"))
    )
    (comp (ref "C66")
      (value "C")
      (footprint "SMD_0402_CAPC1005X70N")
      (fields
        (field (name "DB_PART_NUMBER") "CAP000047481")
        (field (name "DB_VALUE") "10uF")
        (field (name "DB_TOLERANCE") "20%")
        (field (name "DB_VOLTAGE") "10V")
        (field (name "DB_MANUFACTURER_PART") "SAMSUNG    CL05A106MP5NUNC")
        (field (name "DB_APPROVED_BY") "VSN")
      )
      (libsource (lib "Database_Libs1") (part "C"))
    )
    (comp (ref "C67")
      (value "C")
      (footprint "SMD_0402_CAPC1005X70N")
      (fields
        (field (name "DB_PART_NUMBER") "CAP000047481")
        (field (name "DB_VALUE") "10uF")
        (field (name "DB_TOLERANCE") "20%")
        (field (name "DB_VOLTAGE") "10V")
        (field (name "DB_MANUFACTURER_PART") "SAMSUNG    CL05A106MP5NUNC")
        (field (name "DB_APPROVED_BY") "VSN")
      )
      (libsource (lib "Database_Libs1") (part "C"))
    )
    (comp (ref "U1")
      (value "IC_BITFURY16")
      (footprint "SMD_QFN50P600X600X175-36AN")
      (description "BitFury 2016 16 nm")
      (libsource (lib "BitCoin") (part "IC_BITFURY16"))
    )
    (comp (ref "U2")
      (value "IC_BITFURY16")
      (footprint "SMD_QFN50P600X600X175-36AN")
      (description "BitFury 2016 16 nm")
      (libsource (lib "BitCoin") (part "IC_BITFURY16"))
    )
    (comp (ref "U3")
      (value "IC_BITFURY16")
      (footprint "SMD_QFN50P600X600X175-36AN")
      (description "BitFury 2016 16 nm")
      (libsource (lib "BitCoin") (part "IC_BITFURY16"))
    )
    (comp (ref "U4")
      (value "IC_BITFURY16")
      (footprint "SMD_QFN50P600X600X175-36AN")
      (description "BitFury 2016 16 nm")
      (libsource (lib "BitCoin") (part "IC_BITFURY16"))
    )
    (comp (ref "U5")
      (value "IC_BITFURY16")
      (footprint "SMD_QFN50P600X600X175-36AN")
      (description "BitFury 2016 16 nm")
      (libsource (lib "BitCoin") (part "IC_BITFURY16"))
    )
    (comp (ref "U6")
      (value "IC_BITFURY16")
      (footprint "SMD_QFN50P600X600X175-36AN")
      (description "BitFury 2016 16 nm")
      (libsource (lib "BitCoin") (part "IC_BITFURY16"))
    )
    (comp (ref "U7")
      (value "IC_BITFURY16")
      (footprint "SMD_QFN50P600X600X175-36AN")
      (description "BitFury 2016 16 nm")
      (libsource (lib "BitCoin") (part "IC_BITFURY16"))
    )
    (comp (ref "U8")
      (value "IC_BITFURY16")
      (footprint "SMD_QFN50P600X600X175-36AN")
      (description "BitFury 2016 16 nm")
      (libsource (lib "BitCoin") (part "IC_BITFURY16"))
    )
    (comp (ref "U9")
      (value "IC_BTC250")
      (footprint "SMD_QFN40P500X500X80-41N")
      (fields (field (name "DB_MANUFACTURER_PART") "BTC250 QFN40 EP"))
      (libsource (lib "BitCoin") (part "IC_BTC250"))
    )
    (comp (ref "U10")
      (value "IC_BITFURY16")
      (footprint "SMD_QFN50P600X600X175-36AN")
      (description "BitFury 2016 16 nm")
      (libsource (lib "BitCoin") (part "IC_BITFURY16"))
    )
    (comp (ref "U11")
      (value "IC_BITFURY16")
      (footprint "SMD_QFN50P600X600X175-36AN")
      (description "BitFury 2016 16 nm")
      (libsource (lib "BitCoin") (part "IC_BITFURY16"))
    )
    (comp (ref "U12")
      (value "IC_BITFURY16")
      (footprint "SMD_QFN50P600X600X175-36AN")
      (description "BitFury 2016 16 nm")
      (libsource (lib "BitCoin") (part "IC_BITFURY16"))
    )
  )
  (nets
    (net (code "1") (name "/C_0") (class "Default")
      (node (ref "U1") (pin "22") (pinfunction "SCK_22") (pintype "passive"))
      (node (ref "U9") (pin "10") (pinfunction "C_0_10") (pintype "passive"))
    )
    (net (code "2") (name "/C_1") (class "Default")
      (node (ref "U2") (pin "22") (pinfunction "SCK_22") (pintype "passive"))
      (node (ref "U9") (pin "7") (pinfunction "C_1_7") (pintype "passive"))
    )
    (net (code "3") (name "/C_2") (class "Default")
      (node (ref "U3") (pin "22") (pinfunction "SCK_22") (pintype "passive"))
      (node (ref "U9") (pin "4") (pinfunction "C_2_4") (pintype "passive"))
    )
    (net (code "4") (name "/C_3") (class "Default")
      (node (ref "U4") (pin "22") (pinfunction "SCK_22") (pintype "passive"))
      (node (ref "U9") (pin "1") (pinfunction "C_3_1") (pintype "passive"))
    )
    (net (code "5") (name "/C_4") (class "Default")
      (node (ref "U5") (pin "22") (pinfunction "SCK_22") (pintype "passive"))
      (node (ref "U9") (pin "38") (pinfunction "C_4_38") (pintype "passive"))
    )
    (net (code "6") (name "/C_5") (class "Default")
      (node (ref "U6") (pin "22") (pinfunction "SCK_22") (pintype "passive"))
      (node (ref "U9") (pin "35") (pinfunction "C_5_35") (pintype "passive"))
    )
    (net (code "7") (name "/C_6") (class "Default")
      (node (ref "U7") (pin "22") (pinfunction "SCK_22") (pintype "passive"))
      (node (ref "U9") (pin "32") (pinfunction "C_6_32") (pintype "passive"))
    )
    (net (code "8") (name "/C_7") (class "Default")
      (node (ref "U8") (pin "22") (pinfunction "SCK_22") (pintype "passive"))
      (node (ref "U9") (pin "29") (pinfunction "C_7_29") (pintype "passive"))
    )
    (net (code "9") (name "/C_8") (class "Default")
      (node (ref "U10") (pin "22") (pinfunction "SCK_22") (pintype "passive"))
      (node (ref "U9") (pin "26") (pinfunction "C_8_26") (pintype "passive"))
    )
    (net (code "10") (name "/C_9") (class "Default")
      (node (ref "U11") (pin "22") (pinfunction "SCK_22") (pintype "passive"))
      (node (ref "U9") (pin "23") (pinfunction "C_9_23") (pintype "passive"))
    )
    (net (code "11") (name "/C_10") (class "Default")
      (node (ref "U12") (pin "22") (pinfunction "SCK_22") (pintype "passive"))
      (node (ref "U9") (pin "20") (pinfunction "C_10_20") (pintype "passive"))
    )
    (net (code "12") (name "/D_0") (class "Default")
      (node (ref "U1") (pin "23") (pinfunction "SDATA_23") (pintype "passive"))
      (node (ref "U9") (pin "9") (pinfunction "D_0_9") (pintype "passive"))
    )
    (net (code "13") (name "/D_1") (class "Default")
      (node (ref "U2") (pin "23") (pinfunction "SDATA_23") (pintype "passive"))
      (node (ref "U9") (pin "6") (pinfunction "D_1_6") (pintype "passive"))
    )
    (net (code "14") (name "/D_2") (class "Default")
      (node (ref "U3") (pin "23") (pinfunction "SDATA_23") (pintype "passive"))
      (node (ref "U9") (pin "3") (pinfunction "D_2_3") (pintype "passive"))
    )
    (net (code "15") (name "/D_3") (class "Default")
      (node (ref "U4") (pin "23") (pinfunction "SDATA_23") (pintype "passive"))
      (node (ref "U9") (pin "40") (pinfunction "D_3_40") (pintype "passive"))
    )
    (net (code "16") (name "/D_4") (class "Default")
      (node (ref "U5") (pin "23") (pinfunction "SDATA_23") (pintype "passive"))
      (node (ref "U9") (pin "37") (pinfunction "D_4_37") (pintype "passive"))
    )
    (net (code "17") (name "/D_5") (class "Default")
      (node (ref "U6") (pin "23") (pinfunction "SDATA_23") (pintype "passive"))
      (node (ref "U9") (pin "34") (pinfunction "D_5_34") (pintype "passive"))
    )
    (net (code "18") (name "/D_6") (class "Default")
      (node (ref "U7") (pin "23") (pinfunction "SDATA_23") (pintype "passive"))
      (node (ref "U9") (pin "31") (pinfunction "D_6_31") (pintype "passive"))
    )
    (net (code "19") (name "/D_7") (class "Default")
      (node (ref "U8") (pin "23") (pinfunction "SDATA_23") (pintype "passive"))
      (node (ref "U9") (pin "28") (pinfunction "D_7_28") (pintype "passive"))
    )
    (net (code "20") (name "/D_8") (class "Default")
      (node (ref "U10") (pin "23") (pinfunction "SDATA_23") (pintype "passive"))
      (node (ref "U9") (pin "25") (pinfunction "D_8_25") (pintype "passive"))
    )
    (net (code "21") (name "/D_9") (class "Default")
      (node (ref "U11") (pin "23") (pinfunction "SDATA_23") (pintype "passive"))
      (node (ref "U9") (pin "22") (pinfunction "D_9_22") (pintype "passive"))
    )
    (net (code "22") (name "/D_10") (class "Default")
      (node (ref "U12") (pin "23") (pinfunction "SDATA_23") (pintype "passive"))
      (node (ref "U9") (pin "19") (pinfunction "D_10_19") (pintype "passive"))
    )
    (net (code "23") (name "/PAR_3") (class "Default")
      (node (ref "U9") (pin "18") (pinfunction "PARITY_18") (pintype "passive"))
    )
    (net (code "24") (name "/PWR16") (class "Default")
      (node (ref "C1") (pin "2") (pinfunction "2_2") (pintype "passive"))
      (node (ref "C13") (pin "2") (pinfunction "2_2") (pintype "passive"))
      (node (ref "C14") (pin "2") (pinfunction "2_2") (pintype "passive"))
      (node (ref "C15") (pin "2") (pinfunction "2_2") (pintype "passive"))
      (node (ref "C2") (pin "2") (pinfunction "2_2") (pintype "passive"))
      (node (ref "C3") (pin "2") (pinfunction "2_2") (pintype "passive"))
      (node (ref "C49") (pin "2") (pinfunction "2_2") (pintype "passive"))
      (node (ref "U1") (pin "36") (pinfunction "EP_36") (pintype "passive"))
      (node (ref "U9") (pin "41") (pinfunction "VSS_41") (pintype "passive"))
    )
    (net (code "25") (name "/PWR17") (class "Default")
      (node (ref "U9") (pin "8") (pinfunction "V_0_8") (pintype "passive"))
    )
    (net (code "26") (name "/PWR18") (class "Default")
      (node (ref "U9") (pin "5") (pinfunction "V_1_5") (pintype "passive"))
    )
    (net (code "27") (name "/PWR19") (class "Default")
      (node (ref "U9") (pin "2") (pinfunction "V_2_2") (pintype "passive"))
    )
    (net (code "28") (name "/PWR20") (class "Default")
      (node (ref "U9") (pin "39") (pinfunction "V_3_39") (pintype "passive"))
    )
    (net (code "29") (name "/PWR21") (class "Default")
      (node (ref "U9") (pin "36") (pinfunction "V_4_36") (pintype "passive"))
    )
    (net (code "30") (name "/PWR22") (class "Default")
      (node (ref "U9") (pin "33") (pinfunction "V_5_33") (pintype "passive"))
    )
    (net (code "31") (name "/PWR23") (class "Default")
      (node (ref "U9") (pin "30") (pinfunction "V_6_30") (pintype "passive"))
    )
    (net (code "32") (name "/PWR24") (class "Default")
      (node (ref "U9") (pin "27") (pinfunction "V_7_27") (pintype "passive"))
    )
    (net (code "33") (name "/PWR25") (class "Default")
      (node (ref "U9") (pin "24") (pinfunction "V_8_24") (pintype "passive"))
    )
    (net (code "34") (name "/PWR26") (class "Default")
      (node (ref "U9") (pin "21") (pinfunction "V_9_21") (pintype "passive"))
    )
    (net (code "35") (name "/RX0_3") (class "Default")
      (node (ref "U9") (pin "12") (pinfunction "RX_0_12") (pintype "passive"))
    )
    (net (code "36") (name "/RX1_3") (class "Default")
      (node (ref "U9") (pin "14") (pinfunction "RX_1_14") (pintype "passive"))
    )
    (net (code "37") (name "/RX2_3") (class "Default")
      (node (ref "U9") (pin "16") (pinfunction "RX_2_16") (pintype "passive"))
    )
    (net (code "38") (name "/TX0_3") (class "Default")
      (node (ref "U9") (pin "11") (pinfunction "TX_0_11") (pintype "passive"))
    )
    (net (code "39") (name "/TX1_3") (class "Default")
      (node (ref "U9") (pin "13") (pinfunction "TX_1_13") (pintype "passive"))
    )
    (net (code "40") (name "/TX2_3") (class "Default")
      (node (ref "U9") (pin "15") (pinfunction "TX_2_15") (pintype "passive"))
    )
    (net (code "41") (name "/VCC") (class "Default")
      (node (ref "C49") (pin "1") (pinfunction "1_1") (pintype "passive"))
      (node (ref "C56") (pin "1") (pinfunction "1_1") (pintype "passive"))
      (node (ref "C57") (pin "1") (pinfunction "1_1") (pintype "passive"))
      (node (ref "C58") (pin "1") (pinfunction "1_1") (pintype "passive"))
      (node (ref "C65") (pin "1") (pinfunction "1_1") (pintype "passive"))
      (node (ref "C66") (pin "1") (pinfunction "1_1") (pintype "passive"))
      (node (ref "C67") (pin "1") (pinfunction "1_1") (pintype "passive"))
      (node (ref "U12") (pin "1") (pinfunction "VDD_1") (pintype "passive"))
      (node (ref "U12") (pin "10") (pinfunction "VDD_10") (pintype "passive"))
      (node (ref "U12") (pin "11") (pinfunction "VDD_11") (pintype "passive"))
      (node (ref "U12") (pin "12") (pinfunction "VDD_12") (pintype "passive"))
      (node (ref "U12") (pin "13") (pinfunction "VDD_13") (pintype "passive"))
      (node (ref "U12") (pin "14") (pinfunction "VDD_14") (pintype "passive"))
      (node (ref "U12") (pin "15") (pinfunction "VDD_15") (pintype "passive"))
      (node (ref "U12") (pin "16") (pinfunction "VDD_16") (pintype "passive"))
      (node (ref "U12") (pin "17") (pinfunction "VDD_17") (pintype "passive"))
      (node (ref "U12") (pin "18") (pinfunction "VDD_18") (pintype "passive"))
      (node (ref "U12") (pin "19") (pinfunction "VDD_19") (pintype "passive"))
      (node (ref "U12") (pin "2") (pinfunction "VDD_2") (pintype "passive"))
      (node (ref "U12") (pin "20") (pinfunction "VDD_20") (pintype "passive"))
      (node (ref "U12") (pin "21") (pinfunction "VDD_21") (pintype "passive"))
      (node (ref "U12") (pin "24") (pinfunction "VDD_24") (pintype "passive"))
      (node (ref "U12") (pin "25") (pinfunction "VDD_25") (pintype "passive"))
      (node (ref "U12") (pin "26") (pinfunction "VDD_26") (pintype "passive"))
      (node (ref "U12") (pin "27") (pinfunction "VDD_27") (pintype "passive"))
      (node (ref "U12") (pin "28") (pinfunction "VDD_28") (pintype "passive"))
      (node (ref "U12") (pin "29") (pinfunction "VDD_29") (pintype "passive"))
      (node (ref "U12") (pin "3") (pinfunction "VDD_3") (pintype "passive"))
      (node (ref "U12") (pin "30") (pinfunction "VDD_30") (pintype "passive"))
      (node (ref "U12") (pin "31") (pinfunction "VDD_31") (pintype "passive"))
      (node (ref "U12") (pin "32") (pinfunction "VDD_32") (pintype "passive"))
      (node (ref "U12") (pin "33") (pinfunction "VDD_33") (pintype "passive"))
      (node (ref "U12") (pin "34") (pinfunction "VDD_34") (pintype "passive"))
      (node (ref "U12") (pin "35") (pinfunction "VDD_35") (pintype "passive"))
      (node (ref "U12") (pin "4") (pinfunction "VDD_4") (pintype "passive"))
      (node (ref "U12") (pin "5") (pinfunction "VDD_5") (pintype "passive"))
      (node (ref "U12") (pin "6") (pinfunction "VDD_6") (pintype "passive"))
      (node (ref "U12") (pin "7") (pinfunction "VDD_7") (pintype "passive"))
      (node (ref "U12") (pin "8") (pinfunction "VDD_8") (pintype "passive"))
      (node (ref "U12") (pin "9") (pinfunction "VDD_9") (pintype "passive"))
      (node (ref "U9") (pin "17") (pinfunction "VDD_17") (pintype "passive"))
    )
    (net (code "42") (name "/V_0") (class "Default")
      (node (ref "C1") (pin "1") (pinfunction "1_1") (pintype "passive"))
      (node (ref "C13") (pin "1") (pinfunction "1_1") (pintype "passive"))
      (node (ref "C14") (pin "1") (pinfunction "1_1") (pintype "passive"))
      (node (ref "C15") (pin "1") (pinfunction "1_1") (pintype "passive"))
      (node (ref "C16") (pin "2") (pinfunction "2_2") (pintype "passive"))
      (node (ref "C17") (pin "2") (pinfunction "2_2") (pintype "passive"))
      (node (ref "C18") (pin "2") (pinfunction "2_2") (pintype "passive"))
      (node (ref "C2") (pin "1") (pinfunction "1_1") (pintype "passive"))
      (node (ref "C3") (pin "1") (pinfunction "1_1") (pintype "passive"))
      (node (ref "C4") (pin "2") (pinfunction "2_2") (pintype "passive"))
      (node (ref "C5") (pin "2") (pinfunction "2_2") (pintype "passive"))
      (node (ref "C6") (pin "2") (pinfunction "2_2") (pintype "passive"))
      (node (ref "U1") (pin "1") (pinfunction "VDD_1") (pintype "passive"))
      (node (ref "U1") (pin "10") (pinfunction "VDD_10") (pintype "passive"))
      (node (ref "U1") (pin "11") (pinfunction "VDD_11") (pintype "passive"))
      (node (ref "U1") (pin "12") (pinfunction "VDD_12") (pintype "passive"))
      (node (ref "U1") (pin "13") (pinfunction "VDD_13") (pintype "passive"))
      (node (ref "U1") (pin "14") (pinfunction "VDD_14") (pintype "passive"))
      (node (ref "U1") (pin "15") (pinfunction "VDD_15") (pintype "passive"))
      (node (ref "U1") (pin "16") (pinfunction "VDD_16") (pintype "passive"))
      (node (ref "U1") (pin "17") (pinfunction "VDD_17") (pintype "passive"))
      (node (ref "U1") (pin "18") (pinfunction "VDD_18") (pintype "passive"))
      (node (ref "U1") (pin "19") (pinfunction "VDD_19") (pintype "passive"))
      (node (ref "U1") (pin "2") (pinfunction "VDD_2") (pintype "passive"))
      (node (ref "U1") (pin "20") (pinfunction "VDD_20") (pintype "passive"))
      (node (ref "U1") (pin "21") (pinfunction "VDD_21") (pintype "passive"))
      (node (ref "U1") (pin "24") (pinfunction "VDD_24") (pintype "passive"))
      (node (ref "U1") (pin "25") (pinfunction "VDD_25") (pintype "passive"))
      (node (ref "U1") (pin "26") (pinfunction "VDD_26") (pintype "passive"))
      (node (ref "U1") (pin "27") (pinfunction "VDD_27") (pintype "passive"))
      (node (ref "U1") (pin "28") (pinfunction "VDD_28") (pintype "passive"))
      (node (ref "U1") (pin "29") (pinfunction "VDD_29") (pintype "passive"))
      (node (ref "U1") (pin "3") (pinfunction "VDD_3") (pintype "passive"))
      (node (ref "U1") (pin "30") (pinfunction "VDD_30") (pintype "passive"))
      (node (ref "U1") (pin "31") (pinfunction "VDD_31") (pintype "passive"))
      (node (ref "U1") (pin "32") (pinfunction "VDD_32") (pintype "passive"))
      (node (ref "U1") (pin "33") (pinfunction "VDD_33") (pintype "passive"))
      (node (ref "U1") (pin "34") (pinfunction "VDD_34") (pintype "passive"))
      (node (ref "U1") (pin "35") (pinfunction "VDD_35") (pintype "passive"))
      (node (ref "U1") (pin "4") (pinfunction "VDD_4") (pintype "passive"))
      (node (ref "U1") (pin "5") (pinfunction "VDD_5") (pintype "passive"))
      (node (ref "U1") (pin "6") (pinfunction "VDD_6") (pintype "passive"))
      (node (ref "U1") (pin "7") (pinfunction "VDD_7") (pintype "passive"))
      (node (ref "U1") (pin "8") (pinfunction "VDD_8") (pintype "passive"))
      (node (ref "U1") (pin "9") (pinfunction "VDD_9") (pintype "passive"))
      (node (ref "U2") (pin "36") (pinfunction "EP_36") (pintype "passive"))
    )
    (net (code "43") (name "/V_1") (class "Default")
      (node (ref "C16") (pin "1") (pinfunction "1_1") (pintype "passive"))
      (node (ref "C17") (pin "1") (pinfunction "1_1") (pintype "passive"))
      (node (ref "C18") (pin "1") (pinfunction "1_1") (pintype "passive"))
      (node (ref "C19") (pin "2") (pinfunction "2_2") (pintype "passive"))
      (node (ref "C20") (pin "2") (pinfunction "2_2") (pintype "passive"))
      (node (ref "C21") (pin "2") (pinfunction "2_2") (pintype "passive"))
      (node (ref "C4") (pin "1") (pinfunction "1_1") (pintype "passive"))
      (node (ref "C5") (pin "1") (pinfunction "1_1") (pintype "passive"))
      (node (ref "C6") (pin "1") (pinfunction "1_1") (pintype "passive"))
      (node (ref "C7") (pin "2") (pinfunction "2_2") (pintype "passive"))
      (node (ref "C8") (pin "2") (pinfunction "2_2") (pintype "passive"))
      (node (ref "C9") (pin "2") (pinfunction "2_2") (pintype "passive"))
      (node (ref "U2") (pin "1") (pinfunction "VDD_1") (pintype "passive"))
      (node (ref "U2") (pin "10") (pinfunction "VDD_10") (pintype "passive"))
      (node (ref "U2") (pin "11") (pinfunction "VDD_11") (pintype "passive"))
      (node (ref "U2") (pin "12") (pinfunction "VDD_12") (pintype "passive"))
      (node (ref "U2") (pin "13") (pinfunction "VDD_13") (pintype "passive"))
      (node (ref "U2") (pin "14") (pinfunction "VDD_14") (pintype "passive"))
      (node (ref "U2") (pin "15") (pinfunction "VDD_15") (pintype "passive"))
      (node (ref "U2") (pin "16") (pinfunction "VDD_16") (pintype "passive"))
      (node (ref "U2") (pin "17") (pinfunction "VDD_17") (pintype "passive"))
      (node (ref "U2") (pin "18") (pinfunction "VDD_18") (pintype "passive"))
      (node (ref "U2") (pin "19") (pinfunction "VDD_19") (pintype "passive"))
      (node (ref "U2") (pin "2") (pinfunction "VDD_2") (pintype "passive"))
      (node (ref "U2") (pin "20") (pinfunction "VDD_20") (pintype "passive"))
      (node (ref "U2") (pin "21") (pinfunction "VDD_21") (pintype "passive"))
      (node (ref "U2") (pin "24") (pinfunction "VDD_24") (pintype "passive"))
      (node (ref "U2") (pin "25") (pinfunction "VDD_25") (pintype "passive"))
      (node (ref "U2") (pin "26") (pinfunction "VDD_26") (pintype "passive"))
      (node (ref "U2") (pin "27") (pinfunction "VDD_27") (pintype "passive"))
      (node (ref "U2") (pin "28") (pinfunction "VDD_28") (pintype "passive"))
      (node (ref "U2") (pin "29") (pinfunction "VDD_29") (pintype "passive"))
      (node (ref "U2") (pin "3") (pinfunction "VDD_3") (pintype "passive"))
      (node (ref "U2") (pin "30") (pinfunction "VDD_30") (pintype "passive"))
      (node (ref "U2") (pin "31") (pinfunction "VDD_31") (pintype "passive"))
      (node (ref "U2") (pin "32") (pinfunction "VDD_32") (pintype "passive"))
      (node (ref "U2") (pin "33") (pinfunction "VDD_33") (pintype "passive"))
      (node (ref "U2") (pin "34") (pinfunction "VDD_34") (pintype "passive"))
      (node (ref "U2") (pin "35") (pinfunction "VDD_35") (pintype "passive"))
      (node (ref "U2") (pin "4") (pinfunction "VDD_4") (pintype "passive"))
      (node (ref "U2") (pin "5") (pinfunction "VDD_5") (pintype "passive"))
      (node (ref "U2") (pin "6") (pinfunction "VDD_6") (pintype "passive"))
      (node (ref "U2") (pin "7") (pinfunction "VDD_7") (pintype "passive"))
      (node (ref "U2") (pin "8") (pinfunction "VDD_8") (pintype "passive"))
      (node (ref "U2") (pin "9") (pinfunction "VDD_9") (pintype "passive"))
      (node (ref "U3") (pin "36") (pinfunction "EP_36") (pintype "passive"))
    )
    (net (code "44") (name "/V_2") (class "Default")
      (node (ref "C10") (pin "2") (pinfunction "2_2") (pintype "passive"))
      (node (ref "C11") (pin "2") (pinfunction "2_2") (pintype "passive"))
      (node (ref "C12") (pin "2") (pinfunction "2_2") (pintype "passive"))
      (node (ref "C19") (pin "1") (pinfunction "1_1") (pintype "passive"))
      (node (ref "C20") (pin "1") (pinfunction "1_1") (pintype "passive"))
      (node (ref "C21") (pin "1") (pinfunction "1_1") (pintype "passive"))
      (node (ref "C22") (pin "2") (pinfunction "2_2") (pintype "passive"))
      (node (ref "C23") (pin "2") (pinfunction "2_2") (pintype "passive"))
      (node (ref "C24") (pin "2") (pinfunction "2_2") (pintype "passive"))
      (node (ref "C7") (pin "1") (pinfunction "1_1") (pintype "passive"))
      (node (ref "C8") (pin "1") (pinfunction "1_1") (pintype "passive"))
      (node (ref "C9") (pin "1") (pinfunction "1_1") (pintype "passive"))
      (node (ref "U3") (pin "1") (pinfunction "VDD_1") (pintype "passive"))
      (node (ref "U3") (pin "10") (pinfunction "VDD_10") (pintype "passive"))
      (node (ref "U3") (pin "11") (pinfunction "VDD_11") (pintype "passive"))
      (node (ref "U3") (pin "12") (pinfunction "VDD_12") (pintype "passive"))
      (node (ref "U3") (pin "13") (pinfunction "VDD_13") (pintype "passive"))
      (node (ref "U3") (pin "14") (pinfunction "VDD_14") (pintype "passive"))
      (node (ref "U3") (pin "15") (pinfunction "VDD_15") (pintype "passive"))
      (node (ref "U3") (pin "16") (pinfunction "VDD_16") (pintype "passive"))
      (node (ref "U3") (pin "17") (pinfunction "VDD_17") (pintype "passive"))
      (node (ref "U3") (pin "18") (pinfunction "VDD_18") (pintype "passive"))
      (node (ref "U3") (pin "19") (pinfunction "VDD_19") (pintype "passive"))
      (node (ref "U3") (pin "2") (pinfunction "VDD_2") (pintype "passive"))
      (node (ref "U3") (pin "20") (pinfunction "VDD_20") (pintype "passive"))
      (node (ref "U3") (pin "21") (pinfunction "VDD_21") (pintype "passive"))
      (node (ref "U3") (pin "24") (pinfunction "VDD_24") (pintype "passive"))
      (node (ref "U3") (pin "25") (pinfunction "VDD_25") (pintype "passive"))
      (node (ref "U3") (pin "26") (pinfunction "VDD_26") (pintype "passive"))
      (node (ref "U3") (pin "27") (pinfunction "VDD_27") (pintype "passive"))
      (node (ref "U3") (pin "28") (pinfunction "VDD_28") (pintype "passive"))
      (node (ref "U3") (pin "29") (pinfunction "VDD_29") (pintype "passive"))
      (node (ref "U3") (pin "3") (pinfunction "VDD_3") (pintype "passive"))
      (node (ref "U3") (pin "30") (pinfunction "VDD_30") (pintype "passive"))
      (node (ref "U3") (pin "31") (pinfunction "VDD_31") (pintype "passive"))
      (node (ref "U3") (pin "32") (pinfunction "VDD_32") (pintype "passive"))
      (node (ref "U3") (pin "33") (pinfunction "VDD_33") (pintype "passive"))
      (node (ref "U3") (pin "34") (pinfunction "VDD_34") (pintype "passive"))
      (node (ref "U3") (pin "35") (pinfunction "VDD_35") (pintype "passive"))
      (node (ref "U3") (pin "4") (pinfunction "VDD_4") (pintype "passive"))
      (node (ref "U3") (pin "5") (pinfunction "VDD_5") (pintype "passive"))
      (node (ref "U3") (pin "6") (pinfunction "VDD_6") (pintype "passive"))
      (node (ref "U3") (pin "7") (pinfunction "VDD_7") (pintype "passive"))
      (node (ref "U3") (pin "8") (pinfunction "VDD_8") (pintype "passive"))
      (node (ref "U3") (pin "9") (pinfunction "VDD_9") (pintype "passive"))
      (node (ref "U4") (pin "36") (pinfunction "EP_36") (pintype "passive"))
    )
    (net (code "45") (name "/V_3") (class "Default")
      (node (ref "C10") (pin "1") (pinfunction "1_1") (pintype "passive"))
      (node (ref "C11") (pin "1") (pinfunction "1_1") (pintype "passive"))
      (node (ref "C12") (pin "1") (pinfunction "1_1") (pintype "passive"))
      (node (ref "C22") (pin "1") (pinfunction "1_1") (pintype "passive"))
      (node (ref "C23") (pin "1") (pinfunction "1_1") (pintype "passive"))
      (node (ref "C24") (pin "1") (pinfunction "1_1") (pintype "passive"))
      (node (ref "C25") (pin "2") (pinfunction "2_2") (pintype "passive"))
      (node (ref "C26") (pin "2") (pinfunction "2_2") (pintype "passive"))
      (node (ref "C27") (pin "2") (pinfunction "2_2") (pintype "passive"))
      (node (ref "C37") (pin "2") (pinfunction "2_2") (pintype "passive"))
      (node (ref "C38") (pin "2") (pinfunction "2_2") (pintype "passive"))
      (node (ref "C39") (pin "2") (pinfunction "2_2") (pintype "passive"))
      (node (ref "U4") (pin "1") (pinfunction "VDD_1") (pintype "passive"))
      (node (ref "U4") (pin "10") (pinfunction "VDD_10") (pintype "passive"))
      (node (ref "U4") (pin "11") (pinfunction "VDD_11") (pintype "passive"))
      (node (ref "U4") (pin "12") (pinfunction "VDD_12") (pintype "passive"))
      (node (ref "U4") (pin "13") (pinfunction "VDD_13") (pintype "passive"))
      (node (ref "U4") (pin "14") (pinfunction "VDD_14") (pintype "passive"))
      (node (ref "U4") (pin "15") (pinfunction "VDD_15") (pintype "passive"))
      (node (ref "U4") (pin "16") (pinfunction "VDD_16") (pintype "passive"))
      (node (ref "U4") (pin "17") (pinfunction "VDD_17") (pintype "passive"))
      (node (ref "U4") (pin "18") (pinfunction "VDD_18") (pintype "passive"))
      (node (ref "U4") (pin "19") (pinfunction "VDD_19") (pintype "passive"))
      (node (ref "U4") (pin "2") (pinfunction "VDD_2") (pintype "passive"))
      (node (ref "U4") (pin "20") (pinfunction "VDD_20") (pintype "passive"))
      (node (ref "U4") (pin "21") (pinfunction "VDD_21") (pintype "passive"))
      (node (ref "U4") (pin "24") (pinfunction "VDD_24") (pintype "passive"))
      (node (ref "U4") (pin "25") (pinfunction "VDD_25") (pintype "passive"))
      (node (ref "U4") (pin "26") (pinfunction "VDD_26") (pintype "passive"))
      (node (ref "U4") (pin "27") (pinfunction "VDD_27") (pintype "passive"))
      (node (ref "U4") (pin "28") (pinfunction "VDD_28") (pintype "passive"))
      (node (ref "U4") (pin "29") (pinfunction "VDD_29") (pintype "passive"))
      (node (ref "U4") (pin "3") (pinfunction "VDD_3") (pintype "passive"))
      (node (ref "U4") (pin "30") (pinfunction "VDD_30") (pintype "passive"))
      (node (ref "U4") (pin "31") (pinfunction "VDD_31") (pintype "passive"))
      (node (ref "U4") (pin "32") (pinfunction "VDD_32") (pintype "passive"))
      (node (ref "U4") (pin "33") (pinfunction "VDD_33") (pintype "passive"))
      (node (ref "U4") (pin "34") (pinfunction "VDD_34") (pintype "passive"))
      (node (ref "U4") (pin "35") (pinfunction "VDD_35") (pintype "passive"))
      (node (ref "U4") (pin "4") (pinfunction "VDD_4") (pintype "passive"))
      (node (ref "U4") (pin "5") (pinfunction "VDD_5") (pintype "passive"))
      (node (ref "U4") (pin "6") (pinfunction "VDD_6") (pintype "passive"))
      (node (ref "U4") (pin "7") (pinfunction "VDD_7") (pintype "passive"))
      (node (ref "U4") (pin "8") (pinfunction "VDD_8") (pintype "passive"))
      (node (ref "U4") (pin "9") (pinfunction "VDD_9") (pintype "passive"))
      (node (ref "U5") (pin "36") (pinfunction "EP_36") (pintype "passive"))
    )
    (net (code "46") (name "/V_4") (class "Default")
      (node (ref "C25") (pin "1") (pinfunction "1_1") (pintype "passive"))
      (node (ref "C26") (pin "1") (pinfunction "1_1") (pintype "passive"))
      (node (ref "C27") (pin "1") (pinfunction "1_1") (pintype "passive"))
      (node (ref "C28") (pin "2") (pinfunction "2_2") (pintype "passive"))
      (node (ref "C29") (pin "2") (pinfunction "2_2") (pintype "passive"))
      (node (ref "C30") (pin "2") (pinfunction "2_2") (pintype "passive"))
      (node (ref "C37") (pin "1") (pinfunction "1_1") (pintype "passive"))
      (node (ref "C38") (pin "1") (pinfunction "1_1") (pintype "passive"))
      (node (ref "C39") (pin "1") (pinfunction "1_1") (pintype "passive"))
      (node (ref "C40") (pin "2") (pinfunction "2_2") (pintype "passive"))
      (node (ref "C41") (pin "2") (pinfunction "2_2") (pintype "passive"))
      (node (ref "C42") (pin "2") (pinfunction "2_2") (pintype "passive"))
      (node (ref "U5") (pin "1") (pinfunction "VDD_1") (pintype "passive"))
      (node (ref "U5") (pin "10") (pinfunction "VDD_10") (pintype "passive"))
      (node (ref "U5") (pin "11") (pinfunction "VDD_11") (pintype "passive"))
      (node (ref "U5") (pin "12") (pinfunction "VDD_12") (pintype "passive"))
      (node (ref "U5") (pin "13") (pinfunction "VDD_13") (pintype "passive"))
      (node (ref "U5") (pin "14") (pinfunction "VDD_14") (pintype "passive"))
      (node (ref "U5") (pin "15") (pinfunction "VDD_15") (pintype "passive"))
      (node (ref "U5") (pin "16") (pinfunction "VDD_16") (pintype "passive"))
      (node (ref "U5") (pin "17") (pinfunction "VDD_17") (pintype "passive"))
      (node (ref "U5") (pin "18") (pinfunction "VDD_18") (pintype "passive"))
      (node (ref "U5") (pin "19") (pinfunction "VDD_19") (pintype "passive"))
      (node (ref "U5") (pin "2") (pinfunction "VDD_2") (pintype "passive"))
      (node (ref "U5") (pin "20") (pinfunction "VDD_20") (pintype "passive"))
      (node (ref "U5") (pin "21") (pinfunction "VDD_21") (pintype "passive"))
      (node (ref "U5") (pin "24") (pinfunction "VDD_24") (pintype "passive"))
      (node (ref "U5") (pin "25") (pinfunction "VDD_25") (pintype "passive"))
      (node (ref "U5") (pin "26") (pinfunction "VDD_26") (pintype "passive"))
      (node (ref "U5") (pin "27") (pinfunction "VDD_27") (pintype "passive"))
      (node (ref "U5") (pin "28") (pinfunction "VDD_28") (pintype "passive"))
      (node (ref "U5") (pin "29") (pinfunction "VDD_29") (pintype "passive"))
      (node (ref "U5") (pin "3") (pinfunction "VDD_3") (pintype "passive"))
      (node (ref "U5") (pin "30") (pinfunction "VDD_30") (pintype "passive"))
      (node (ref "U5") (pin "31") (pinfunction "VDD_31") (pintype "passive"))
      (node (ref "U5") (pin "32") (pinfunction "VDD_32") (pintype "passive"))
      (node (ref "U5") (pin "33") (pinfunction "VDD_33") (pintype "passive"))
      (node (ref "U5") (pin "34") (pinfunction "VDD_34") (pintype "passive"))
      (node (ref "U5") (pin "35") (pinfunction "VDD_35") (pintype "passive"))
      (node (ref "U5") (pin "4") (pinfunction "VDD_4") (pintype "passive"))
      (node (ref "U5") (pin "5") (pinfunction "VDD_5") (pintype "passive"))
      (node (ref "U5") (pin "6") (pinfunction "VDD_6") (pintype "passive"))
      (node (ref "U5") (pin "7") (pinfunction "VDD_7") (pintype "passive"))
      (node (ref "U5") (pin "8") (pinfunction "VDD_8") (pintype "passive"))
      (node (ref "U5") (pin "9") (pinfunction "VDD_9") (pintype "passive"))
      (node (ref "U6") (pin "36") (pinfunction "EP_36") (pintype "passive"))
    )
    (net (code "47") (name "/V_5") (class "Default")
      (node (ref "C28") (pin "1") (pinfunction "1_1") (pintype "passive"))
      (node (ref "C29") (pin "1") (pinfunction "1_1") (pintype "passive"))
      (node (ref "C30") (pin "1") (pinfunction "1_1") (pintype "passive"))
      (node (ref "C31") (pin "2") (pinfunction "2_2") (pintype "passive"))
      (node (ref "C32") (pin "2") (pinfunction "2_2") (pintype "passive"))
      (node (ref "C33") (pin "2") (pinfunction "2_2") (pintype "passive"))
      (node (ref "C40") (pin "1") (pinfunction "1_1") (pintype "passive"))
      (node (ref "C41") (pin "1") (pinfunction "1_1") (pintype "passive"))
      (node (ref "C42") (pin "1") (pinfunction "1_1") (pintype "passive"))
      (node (ref "C43") (pin "2") (pinfunction "2_2") (pintype "passive"))
      (node (ref "C44") (pin "2") (pinfunction "2_2") (pintype "passive"))
      (node (ref "C45") (pin "2") (pinfunction "2_2") (pintype "passive"))
      (node (ref "U6") (pin "1") (pinfunction "VDD_1") (pintype "passive"))
      (node (ref "U6") (pin "10") (pinfunction "VDD_10") (pintype "passive"))
      (node (ref "U6") (pin "11") (pinfunction "VDD_11") (pintype "passive"))
      (node (ref "U6") (pin "12") (pinfunction "VDD_12") (pintype "passive"))
      (node (ref "U6") (pin "13") (pinfunction "VDD_13") (pintype "passive"))
      (node (ref "U6") (pin "14") (pinfunction "VDD_14") (pintype "passive"))
      (node (ref "U6") (pin "15") (pinfunction "VDD_15") (pintype "passive"))
      (node (ref "U6") (pin "16") (pinfunction "VDD_16") (pintype "passive"))
      (node (ref "U6") (pin "17") (pinfunction "VDD_17") (pintype "passive"))
      (node (ref "U6") (pin "18") (pinfunction "VDD_18") (pintype "passive"))
      (node (ref "U6") (pin "19") (pinfunction "VDD_19") (pintype "passive"))
      (node (ref "U6") (pin "2") (pinfunction "VDD_2") (pintype "passive"))
      (node (ref "U6") (pin "20") (pinfunction "VDD_20") (pintype "passive"))
      (node (ref "U6") (pin "21") (pinfunction "VDD_21") (pintype "passive"))
      (node (ref "U6") (pin "24") (pinfunction "VDD_24") (pintype "passive"))
      (node (ref "U6") (pin "25") (pinfunction "VDD_25") (pintype "passive"))
      (node (ref "U6") (pin "26") (pinfunction "VDD_26") (pintype "passive"))
      (node (ref "U6") (pin "27") (pinfunction "VDD_27") (pintype "passive"))
      (node (ref "U6") (pin "28") (pinfunction "VDD_28") (pintype "passive"))
      (node (ref "U6") (pin "29") (pinfunction "VDD_29") (pintype "passive"))
      (node (ref "U6") (pin "3") (pinfunction "VDD_3") (pintype "passive"))
      (node (ref "U6") (pin "30") (pinfunction "VDD_30") (pintype "passive"))
      (node (ref "U6") (pin "31") (pinfunction "VDD_31") (pintype "passive"))
      (node (ref "U6") (pin "32") (pinfunction "VDD_32") (pintype "passive"))
      (node (ref "U6") (pin "33") (pinfunction "VDD_33") (pintype "passive"))
      (node (ref "U6") (pin "34") (pinfunction "VDD_34") (pintype "passive"))
      (node (ref "U6") (pin "35") (pinfunction "VDD_35") (pintype "passive"))
      (node (ref "U6") (pin "4") (pinfunction "VDD_4") (pintype "passive"))
      (node (ref "U6") (pin "5") (pinfunction "VDD_5") (pintype "passive"))
      (node (ref "U6") (pin "6") (pinfunction "VDD_6") (pintype "passive"))
      (node (ref "U6") (pin "7") (pinfunction "VDD_7") (pintype "passive"))
      (node (ref "U6") (pin "8") (pinfunction "VDD_8") (pintype "passive"))
      (node (ref "U6") (pin "9") (pinfunction "VDD_9") (pintype "passive"))
      (node (ref "U7") (pin "36") (pinfunction "EP_36") (pintype "passive"))
    )
    (net (code "48") (name "/V_6") (class "Default")
      (node (ref "C31") (pin "1") (pinfunction "1_1") (pintype "passive"))
      (node (ref "C32") (pin "1") (pinfunction "1_1") (pintype "passive"))
      (node (ref "C33") (pin "1") (pinfunction "1_1") (pintype "passive"))
      (node (ref "C34") (pin "2") (pinfunction "2_2") (pintype "passive"))
      (node (ref "C35") (pin "2") (pinfunction "2_2") (pintype "passive"))
      (node (ref "C36") (pin "2") (pinfunction "2_2") (pintype "passive"))
      (node (ref "C43") (pin "1") (pinfunction "1_1") (pintype "passive"))
      (node (ref "C44") (pin "1") (pinfunction "1_1") (pintype "passive"))
      (node (ref "C45") (pin "1") (pinfunction "1_1") (pintype "passive"))
      (node (ref "C46") (pin "2") (pinfunction "2_2") (pintype "passive"))
      (node (ref "C47") (pin "2") (pinfunction "2_2") (pintype "passive"))
      (node (ref "C48") (pin "2") (pinfunction "2_2") (pintype "passive"))
      (node (ref "U7") (pin "1") (pinfunction "VDD_1") (pintype "passive"))
      (node (ref "U7") (pin "10") (pinfunction "VDD_10") (pintype "passive"))
      (node (ref "U7") (pin "11") (pinfunction "VDD_11") (pintype "passive"))
      (node (ref "U7") (pin "12") (pinfunction "VDD_12") (pintype "passive"))
      (node (ref "U7") (pin "13") (pinfunction "VDD_13") (pintype "passive"))
      (node (ref "U7") (pin "14") (pinfunction "VDD_14") (pintype "passive"))
      (node (ref "U7") (pin "15") (pinfunction "VDD_15") (pintype "passive"))
      (node (ref "U7") (pin "16") (pinfunction "VDD_16") (pintype "passive"))
      (node (ref "U7") (pin "17") (pinfunction "VDD_17") (pintype "passive"))
      (node (ref "U7") (pin "18") (pinfunction "VDD_18") (pintype "passive"))
      (node (ref "U7") (pin "19") (pinfunction "VDD_19") (pintype "passive"))
      (node (ref "U7") (pin "2") (pinfunction "VDD_2") (pintype "passive"))
      (node (ref "U7") (pin "20") (pinfunction "VDD_20") (pintype "passive"))
      (node (ref "U7") (pin "21") (pinfunction "VDD_21") (pintype "passive"))
      (node (ref "U7") (pin "24") (pinfunction "VDD_24") (pintype "passive"))
      (node (ref "U7") (pin "25") (pinfunction "VDD_25") (pintype "passive"))
      (node (ref "U7") (pin "26") (pinfunction "VDD_26") (pintype "passive"))
      (node (ref "U7") (pin "27") (pinfunction "VDD_27") (pintype "passive"))
      (node (ref "U7") (pin "28") (pinfunction "VDD_28") (pintype "passive"))
      (node (ref "U7") (pin "29") (pinfunction "VDD_29") (pintype "passive"))
      (node (ref "U7") (pin "3") (pinfunction "VDD_3") (pintype "passive"))
      (node (ref "U7") (pin "30") (pinfunction "VDD_30") (pintype "passive"))
      (node (ref "U7") (pin "31") (pinfunction "VDD_31") (pintype "passive"))
      (node (ref "U7") (pin "32") (pinfunction "VDD_32") (pintype "passive"))
      (node (ref "U7") (pin "33") (pinfunction "VDD_33") (pintype "passive"))
      (node (ref "U7") (pin "34") (pinfunction "VDD_34") (pintype "passive"))
      (node (ref "U7") (pin "35") (pinfunction "VDD_35") (pintype "passive"))
      (node (ref "U7") (pin "4") (pinfunction "VDD_4") (pintype "passive"))
      (node (ref "U7") (pin "5") (pinfunction "VDD_5") (pintype "passive"))
      (node (ref "U7") (pin "6") (pinfunction "VDD_6") (pintype "passive"))
      (node (ref "U7") (pin "7") (pinfunction "VDD_7") (pintype "passive"))
      (node (ref "U7") (pin "8") (pinfunction "VDD_8") (pintype "passive"))
      (node (ref "U7") (pin "9") (pinfunction "VDD_9") (pintype "passive"))
      (node (ref "U8") (pin "36") (pinfunction "EP_36") (pintype "passive"))
    )
    (net (code "49") (name "/V_7") (class "Default")
      (node (ref "C34") (pin "1") (pinfunction "1_1") (pintype "passive"))
      (node (ref "C35") (pin "1") (pinfunction "1_1") (pintype "passive"))
      (node (ref "C36") (pin "1") (pinfunction "1_1") (pintype "passive"))
      (node (ref "C46") (pin "1") (pinfunction "1_1") (pintype "passive"))
      (node (ref "C47") (pin "1") (pinfunction "1_1") (pintype "passive"))
      (node (ref "C48") (pin "1") (pinfunction "1_1") (pintype "passive"))
      (node (ref "C50") (pin "2") (pinfunction "2_2") (pintype "passive"))
      (node (ref "C51") (pin "2") (pinfunction "2_2") (pintype "passive"))
      (node (ref "C52") (pin "2") (pinfunction "2_2") (pintype "passive"))
      (node (ref "C59") (pin "2") (pinfunction "2_2") (pintype "passive"))
      (node (ref "C60") (pin "2") (pinfunction "2_2") (pintype "passive"))
      (node (ref "C61") (pin "2") (pinfunction "2_2") (pintype "passive"))
      (node (ref "U10") (pin "36") (pinfunction "EP_36") (pintype "passive"))
      (node (ref "U8") (pin "1") (pinfunction "VDD_1") (pintype "passive"))
      (node (ref "U8") (pin "10") (pinfunction "VDD_10") (pintype "passive"))
      (node (ref "U8") (pin "11") (pinfunction "VDD_11") (pintype "passive"))
      (node (ref "U8") (pin "12") (pinfunction "VDD_12") (pintype "passive"))
      (node (ref "U8") (pin "13") (pinfunction "VDD_13") (pintype "passive"))
      (node (ref "U8") (pin "14") (pinfunction "VDD_14") (pintype "passive"))
      (node (ref "U8") (pin "15") (pinfunction "VDD_15") (pintype "passive"))
      (node (ref "U8") (pin "16") (pinfunction "VDD_16") (pintype "passive"))
      (node (ref "U8") (pin "17") (pinfunction "VDD_17") (pintype "passive"))
      (node (ref "U8") (pin "18") (pinfunction "VDD_18") (pintype "passive"))
      (node (ref "U8") (pin "19") (pinfunction "VDD_19") (pintype "passive"))
      (node (ref "U8") (pin "2") (pinfunction "VDD_2") (pintype "passive"))
      (node (ref "U8") (pin "20") (pinfunction "VDD_20") (pintype "passive"))
      (node (ref "U8") (pin "21") (pinfunction "VDD_21") (pintype "passive"))
      (node (ref "U8") (pin "24") (pinfunction "VDD_24") (pintype "passive"))
      (node (ref "U8") (pin "25") (pinfunction "VDD_25") (pintype "passive"))
      (node (ref "U8") (pin "26") (pinfunction "VDD_26") (pintype "passive"))
      (node (ref "U8") (pin "27") (pinfunction "VDD_27") (pintype "passive"))
      (node (ref "U8") (pin "28") (pinfunction "VDD_28") (pintype "passive"))
      (node (ref "U8") (pin "29") (pinfunction "VDD_29") (pintype "passive"))
      (node (ref "U8") (pin "3") (pinfunction "VDD_3") (pintype "passive"))
      (node (ref "U8") (pin "30") (pinfunction "VDD_30") (pintype "passive"))
      (node (ref "U8") (pin "31") (pinfunction "VDD_31") (pintype "passive"))
      (node (ref "U8") (pin "32") (pinfunction "VDD_32") (pintype "passive"))
      (node (ref "U8") (pin "33") (pinfunction "VDD_33") (pintype "passive"))
      (node (ref "U8") (pin "34") (pinfunction "VDD_34") (pintype "passive"))
      (node (ref "U8") (pin "35") (pinfunction "VDD_35") (pintype "passive"))
      (node (ref "U8") (pin "4") (pinfunction "VDD_4") (pintype "passive"))
      (node (ref "U8") (pin "5") (pinfunction "VDD_5") (pintype "passive"))
      (node (ref "U8") (pin "6") (pinfunction "VDD_6") (pintype "passive"))
      (node (ref "U8") (pin "7") (pinfunction "VDD_7") (pintype "passive"))
      (node (ref "U8") (pin "8") (pinfunction "VDD_8") (pintype "passive"))
      (node (ref "U8") (pin "9") (pinfunction "VDD_9") (pintype "passive"))
    )
    (net (code "50") (name "/V_8") (class "Default")
      (node (ref "C50") (pin "1") (pinfunction "1_1") (pintype "passive"))
      (node (ref "C51") (pin "1") (pinfunction "1_1") (pintype "passive"))
      (node (ref "C52") (pin "1") (pinfunction "1_1") (pintype "passive"))
      (node (ref "C53") (pin "2") (pinfunction "2_2") (pintype "passive"))
      (node (ref "C54") (pin "2") (pinfunction "2_2") (pintype "passive"))
      (node (ref "C55") (pin "2") (pinfunction "2_2") (pintype "passive"))
      (node (ref "C59") (pin "1") (pinfunction "1_1") (pintype "passive"))
      (node (ref "C60") (pin "1") (pinfunction "1_1") (pintype "passive"))
      (node (ref "C61") (pin "1") (pinfunction "1_1") (pintype "passive"))
      (node (ref "C62") (pin "2") (pinfunction "2_2") (pintype "passive"))
      (node (ref "C63") (pin "2") (pinfunction "2_2") (pintype "passive"))
      (node (ref "C64") (pin "2") (pinfunction "2_2") (pintype "passive"))
      (node (ref "U10") (pin "1") (pinfunction "VDD_1") (pintype "passive"))
      (node (ref "U10") (pin "10") (pinfunction "VDD_10") (pintype "passive"))
      (node (ref "U10") (pin "11") (pinfunction "VDD_11") (pintype "passive"))
      (node (ref "U10") (pin "12") (pinfunction "VDD_12") (pintype "passive"))
      (node (ref "U10") (pin "13") (pinfunction "VDD_13") (pintype "passive"))
      (node (ref "U10") (pin "14") (pinfunction "VDD_14") (pintype "passive"))
      (node (ref "U10") (pin "15") (pinfunction "VDD_15") (pintype "passive"))
      (node (ref "U10") (pin "16") (pinfunction "VDD_16") (pintype "passive"))
      (node (ref "U10") (pin "17") (pinfunction "VDD_17") (pintype "passive"))
      (node (ref "U10") (pin "18") (pinfunction "VDD_18") (pintype "passive"))
      (node (ref "U10") (pin "19") (pinfunction "VDD_19") (pintype "passive"))
      (node (ref "U10") (pin "2") (pinfunction "VDD_2") (pintype "passive"))
      (node (ref "U10") (pin "20") (pinfunction "VDD_20") (pintype "passive"))
      (node (ref "U10") (pin "21") (pinfunction "VDD_21") (pintype "passive"))
      (node (ref "U10") (pin "24") (pinfunction "VDD_24") (pintype "passive"))
      (node (ref "U10") (pin "25") (pinfunction "VDD_25") (pintype "passive"))
      (node (ref "U10") (pin "26") (pinfunction "VDD_26") (pintype "passive"))
      (node (ref "U10") (pin "27") (pinfunction "VDD_27") (pintype "passive"))
      (node (ref "U10") (pin "28") (pinfunction "VDD_28") (pintype "passive"))
      (node (ref "U10") (pin "29") (pinfunction "VDD_29") (pintype "passive"))
      (node (ref "U10") (pin "3") (pinfunction "VDD_3") (pintype "passive"))
      (node (ref "U10") (pin "30") (pinfunction "VDD_30") (pintype "passive"))
      (node (ref "U10") (pin "31") (pinfunction "VDD_31") (pintype "passive"))
      (node (ref "U10") (pin "32") (pinfunction "VDD_32") (pintype "passive"))
      (node (ref "U10") (pin "33") (pinfunction "VDD_33") (pintype "passive"))
      (node (ref "U10") (pin "34") (pinfunction "VDD_34") (pintype "passive"))
      (node (ref "U10") (pin "35") (pinfunction "VDD_35") (pintype "passive"))
      (node (ref "U10") (pin "4") (pinfunction "VDD_4") (pintype "passive"))
      (node (ref "U10") (pin "5") (pinfunction "VDD_5") (pintype "passive"))
      (node (ref "U10") (pin "6") (pinfunction "VDD_6") (pintype "passive"))
      (node (ref "U10") (pin "7") (pinfunction "VDD_7") (pintype "passive"))
      (node (ref "U10") (pin "8") (pinfunction "VDD_8") (pintype "passive"))
      (node (ref "U10") (pin "9") (pinfunction "VDD_9") (pintype "passive"))
      (node (ref "U11") (pin "36") (pinfunction "EP_36") (pintype "passive"))
    )
    (net (code "51") (name "/V_9") (class "Default")
      (node (ref "C53") (pin "1") (pinfunction "1_1") (pintype "passive"))
      (node (ref "C54") (pin "1") (pinfunction "1_1") (pintype "passive"))
      (node (ref "C55") (pin "1") (pinfunction "1_1") (pintype "passive"))
      (node (ref "C56") (pin "2") (pinfunction "2_2") (pintype "passive"))
      (node (ref "C57") (pin "2") (pinfunction "2_2") (pintype "passive"))
      (node (ref "C58") (pin "2") (pinfunction "2_2") (pintype "passive"))
      (node (ref "C62") (pin "1") (pinfunction "1_1") (pintype "passive"))
      (node (ref "C63") (pin "1") (pinfunction "1_1") (pintype "passive"))
      (node (ref "C64") (pin "1") (pinfunction "1_1") (pintype "passive"))
      (node (ref "C65") (pin "2") (pinfunction "2_2") (pintype "passive"))
      (node (ref "C66") (pin "2") (pinfunction "2_2") (pintype "passive"))
      (node (ref "C67") (pin "2") (pinfunction "2_2") (pintype "passive"))
      (node (ref "U11") (pin "1") (pinfunction "VDD_1") (pintype "passive"))
      (node (ref "U11") (pin "10") (pinfunction "VDD_10") (pintype "passive"))
      (node (ref "U11") (pin "11") (pinfunction "VDD_11") (pintype "passive"))
      (node (ref "U11") (pin "12") (pinfunction "VDD_12") (pintype "passive"))
      (node (ref "U11") (pin "13") (pinfunction "VDD_13") (pintype "passive"))
      (node (ref "U11") (pin "14") (pinfunction "VDD_14") (pintype "passive"))
      (node (ref "U11") (pin "15") (pinfunction "VDD_15") (pintype "passive"))
      (node (ref "U11") (pin "16") (pinfunction "VDD_16") (pintype "passive"))
      (node (ref "U11") (pin "17") (pinfunction "VDD_17") (pintype "passive"))
      (node (ref "U11") (pin "18") (pinfunction "VDD_18") (pintype "passive"))
      (node (ref "U11") (pin "19") (pinfunction "VDD_19") (pintype "passive"))
      (node (ref "U11") (pin "2") (pinfunction "VDD_2") (pintype "passive"))
      (node (ref "U11") (pin "20") (pinfunction "VDD_20") (pintype "passive"))
      (node (ref "U11") (pin "21") (pinfunction "VDD_21") (pintype "passive"))
      (node (ref "U11") (pin "24") (pinfunction "VDD_24") (pintype "passive"))
      (node (ref "U11") (pin "25") (pinfunction "VDD_25") (pintype "passive"))
      (node (ref "U11") (pin "26") (pinfunction "VDD_26") (pintype "passive"))
      (node (ref "U11") (pin "27") (pinfunction "VDD_27") (pintype "passive"))
      (node (ref "U11") (pin "28") (pinfunction "VDD_28") (pintype "passive"))
      (node (ref "U11") (pin "29") (pinfunction "VDD_29") (pintype "passive"))
      (node (ref "U11") (pin "3") (pinfunction "VDD_3") (pintype "passive"))
      (node (ref "U11") (pin "30") (pinfunction "VDD_30") (pintype "passive"))
      (node (ref "U11") (pin "31") (pinfunction "VDD_31") (pintype "passive"))
      (node (ref "U11") (pin "32") (pinfunction "VDD_32") (pintype "passive"))
      (node (ref "U11") (pin "33") (pinfunction "VDD_33") (pintype "passive"))
      (node (ref "U11") (pin "34") (pinfunction "VDD_34") (pintype "passive"))
      (node (ref "U11") (pin "35") (pinfunction "VDD_35") (pintype "passive"))
      (node (ref "U11") (pin "4") (pinfunction "VDD_4") (pintype "passive"))
      (node (ref "U11") (pin "5") (pinfunction "VDD_5") (pintype "passive"))
      (node (ref "U11") (pin "6") (pinfunction "VDD_6") (pintype "passive"))
      (node (ref "U11") (pin "7") (pinfunction "VDD_7") (pintype "passive"))
      (node (ref "U11") (pin "8") (pinfunction "VDD_8") (pintype "passive"))
      (node (ref "U11") (pin "9") (pinfunction "VDD_9") (pintype "passive"))
      (node (ref "U12") (pin "36") (pinfunction "EP_36") (pintype "passive"))
    )
  )
)
